# interfacez_main_r2_5.net
KiCad netlist of a schematic drawn in EAGLE
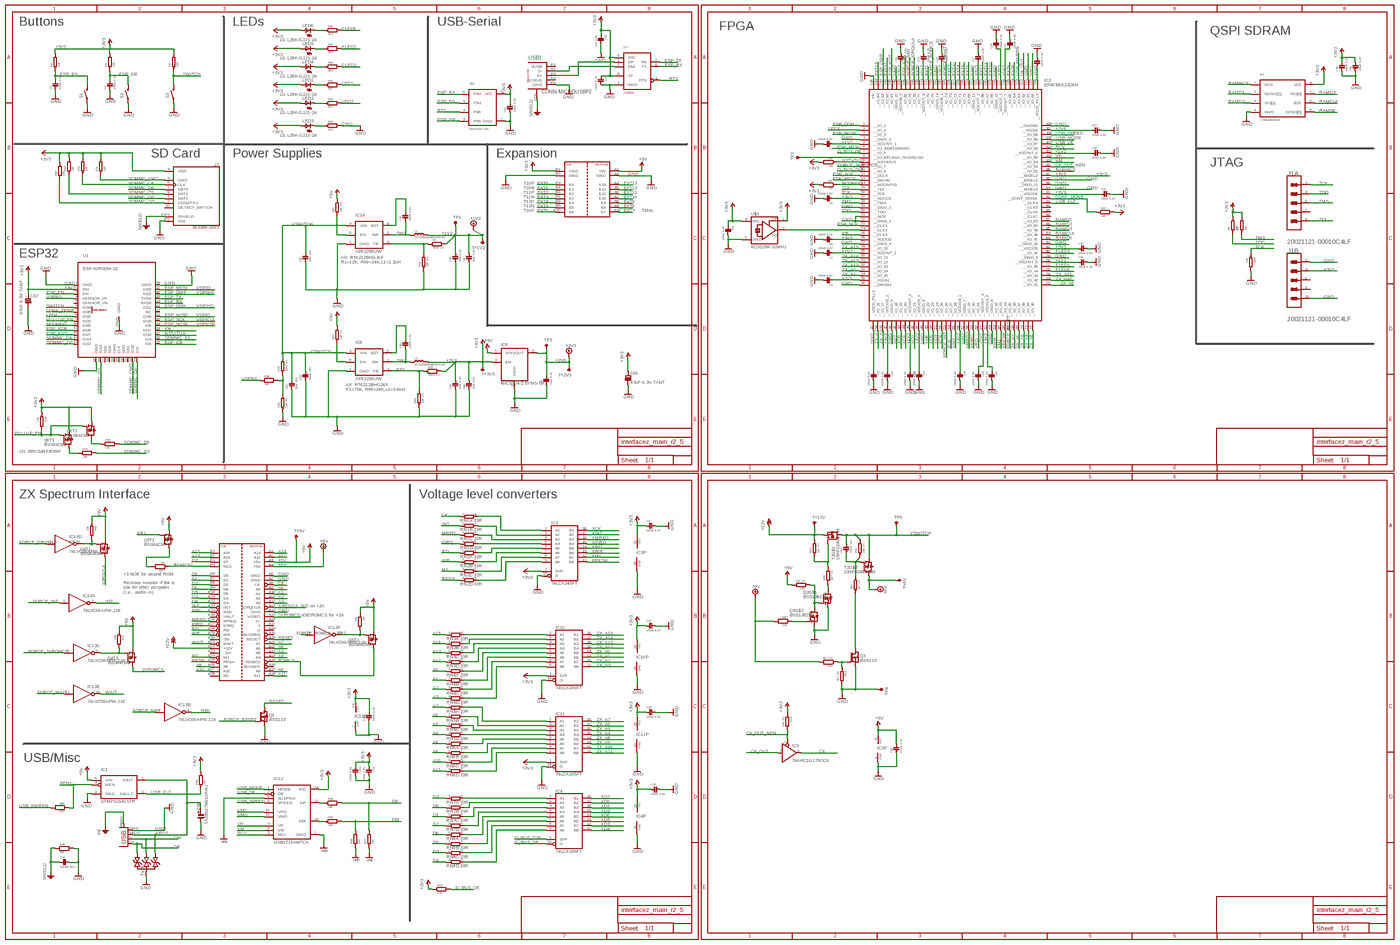
[diagram p0: schematic, sheet 1, overview]
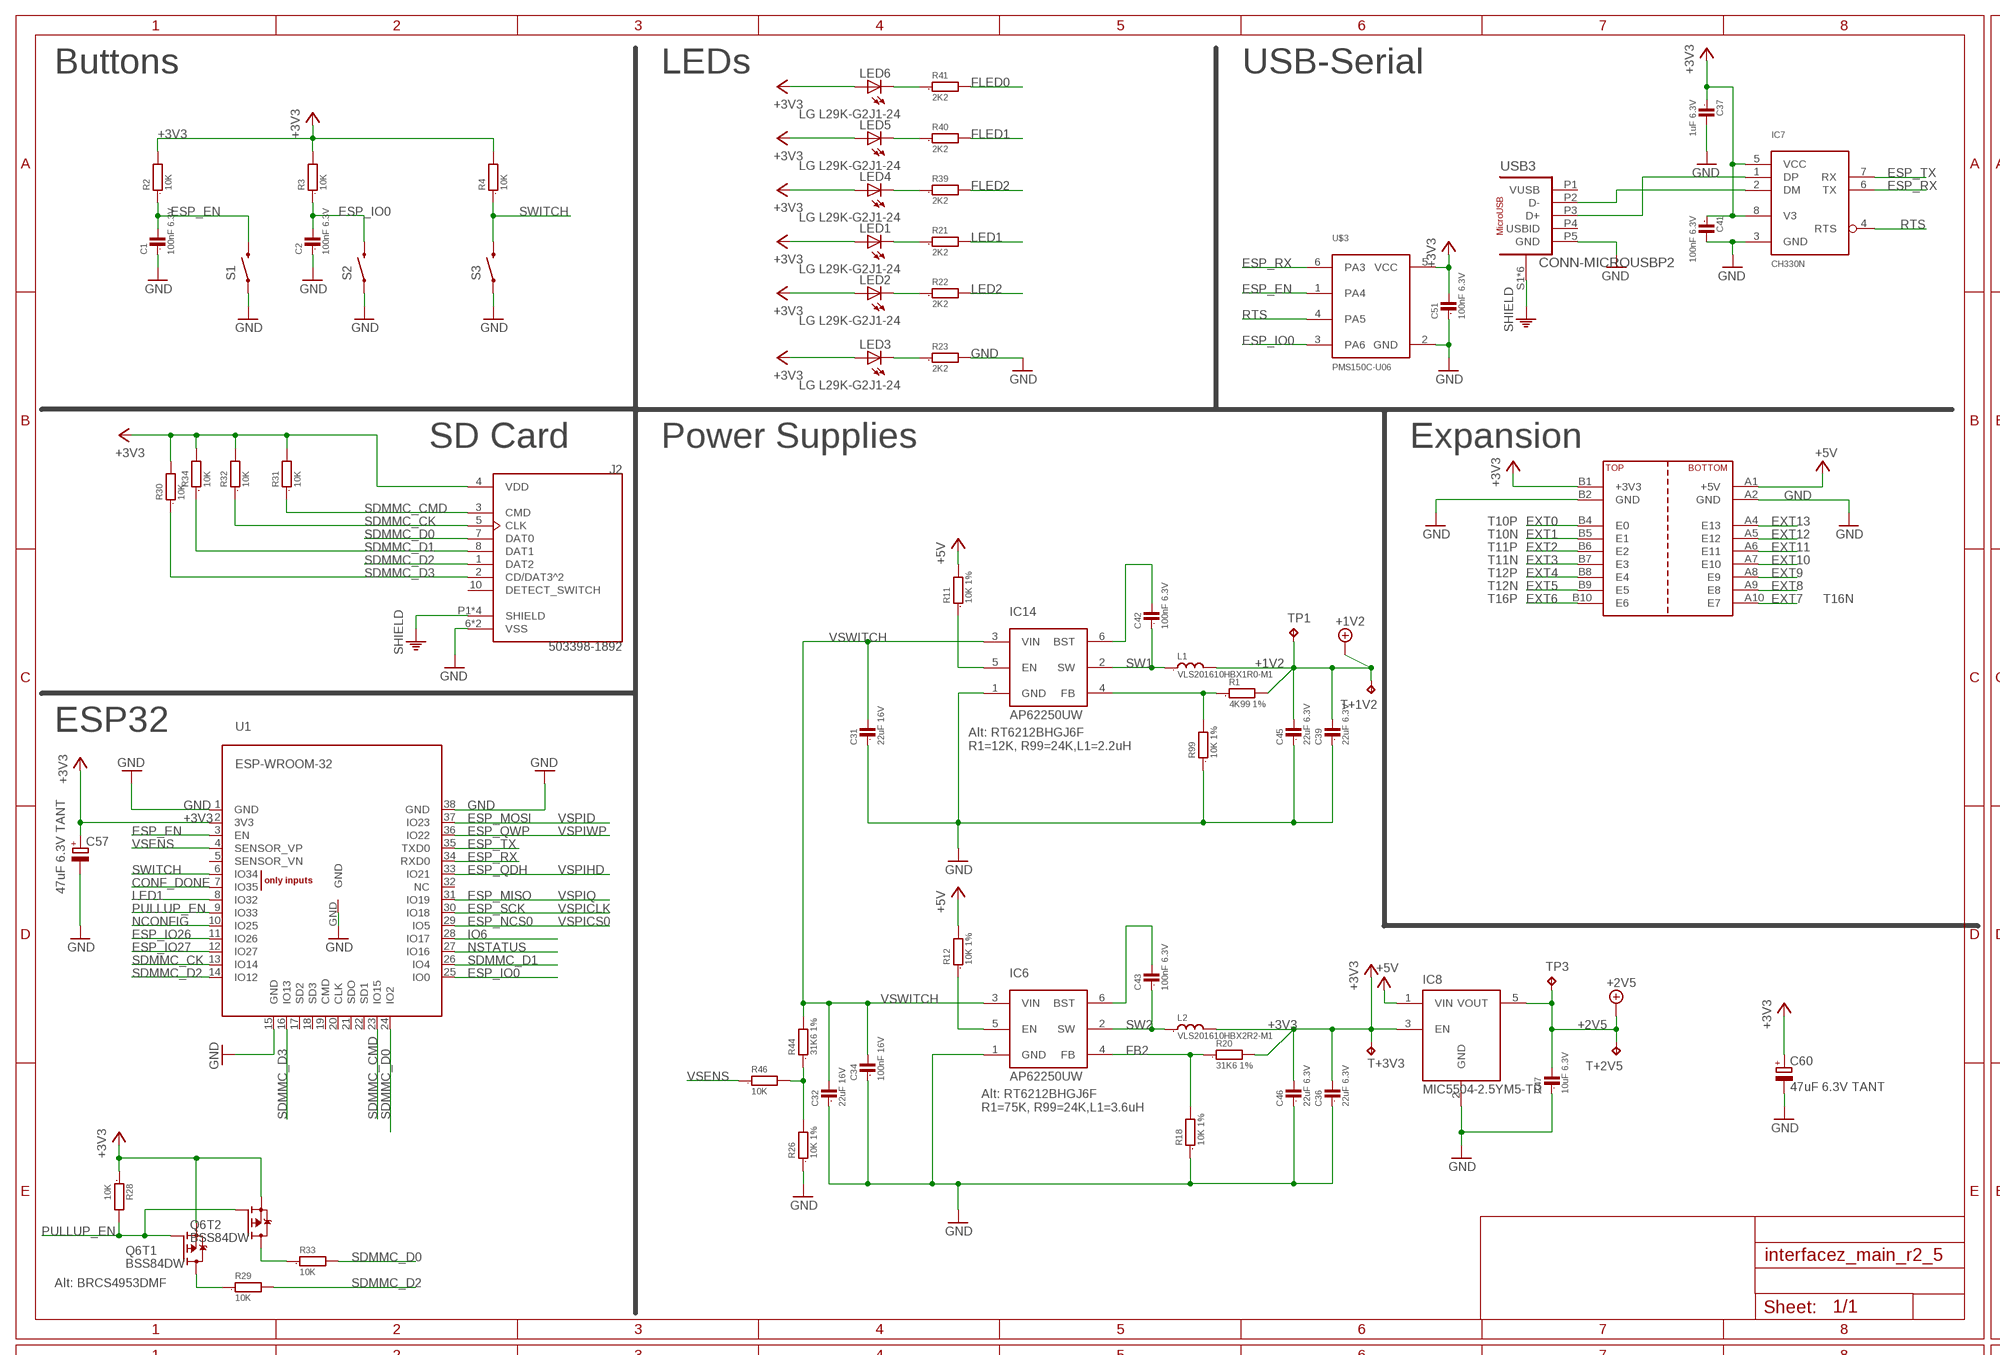
[diagram p1: schematic, sheet 1, part 1 of 4]
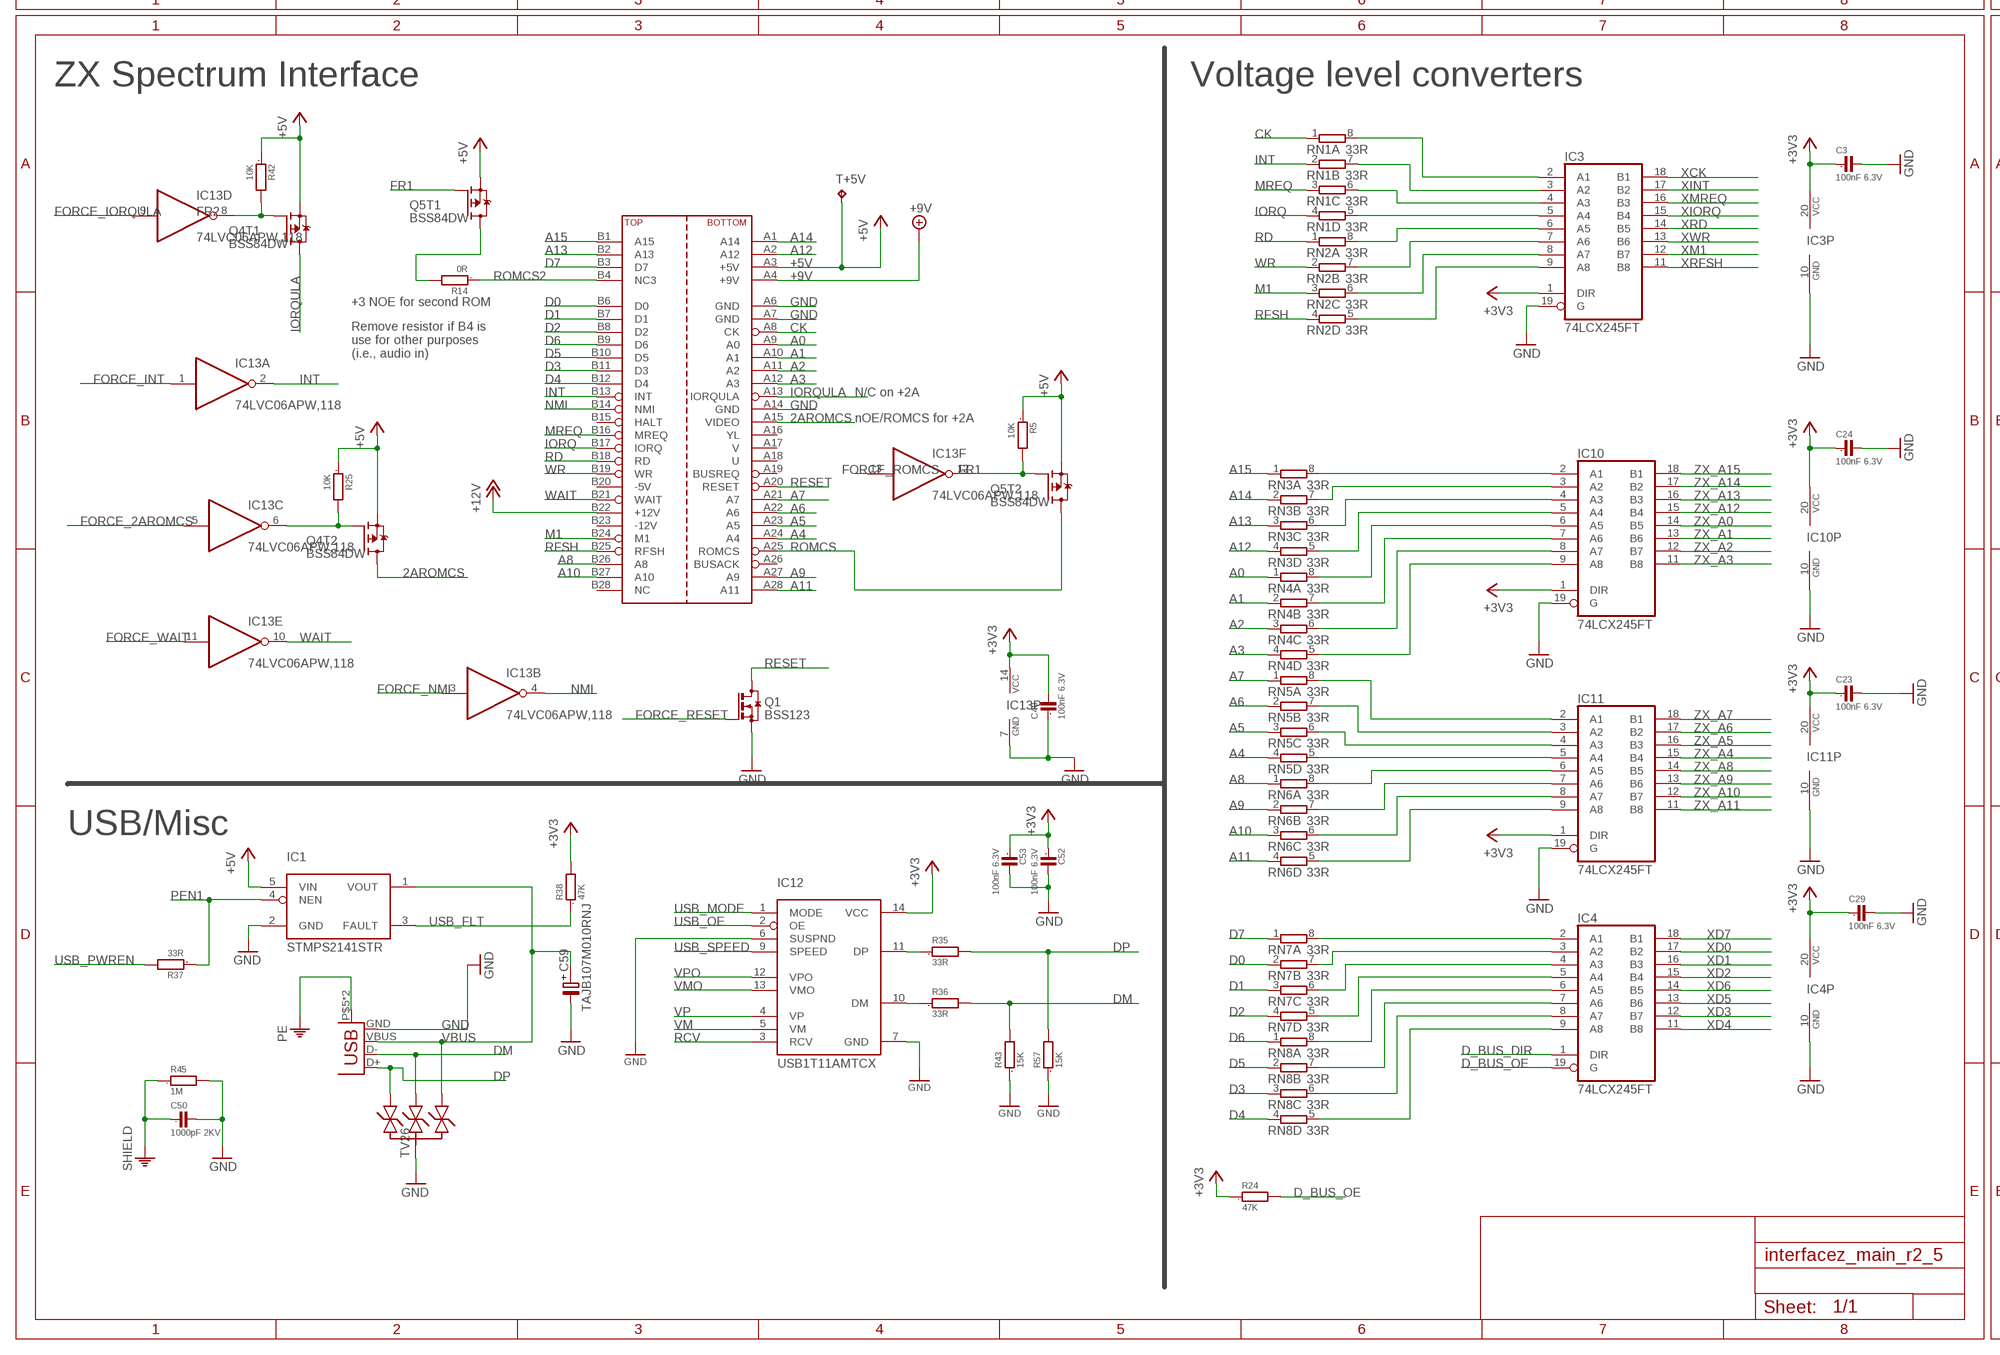
[diagram p2: schematic, sheet 1, part 2 of 4]
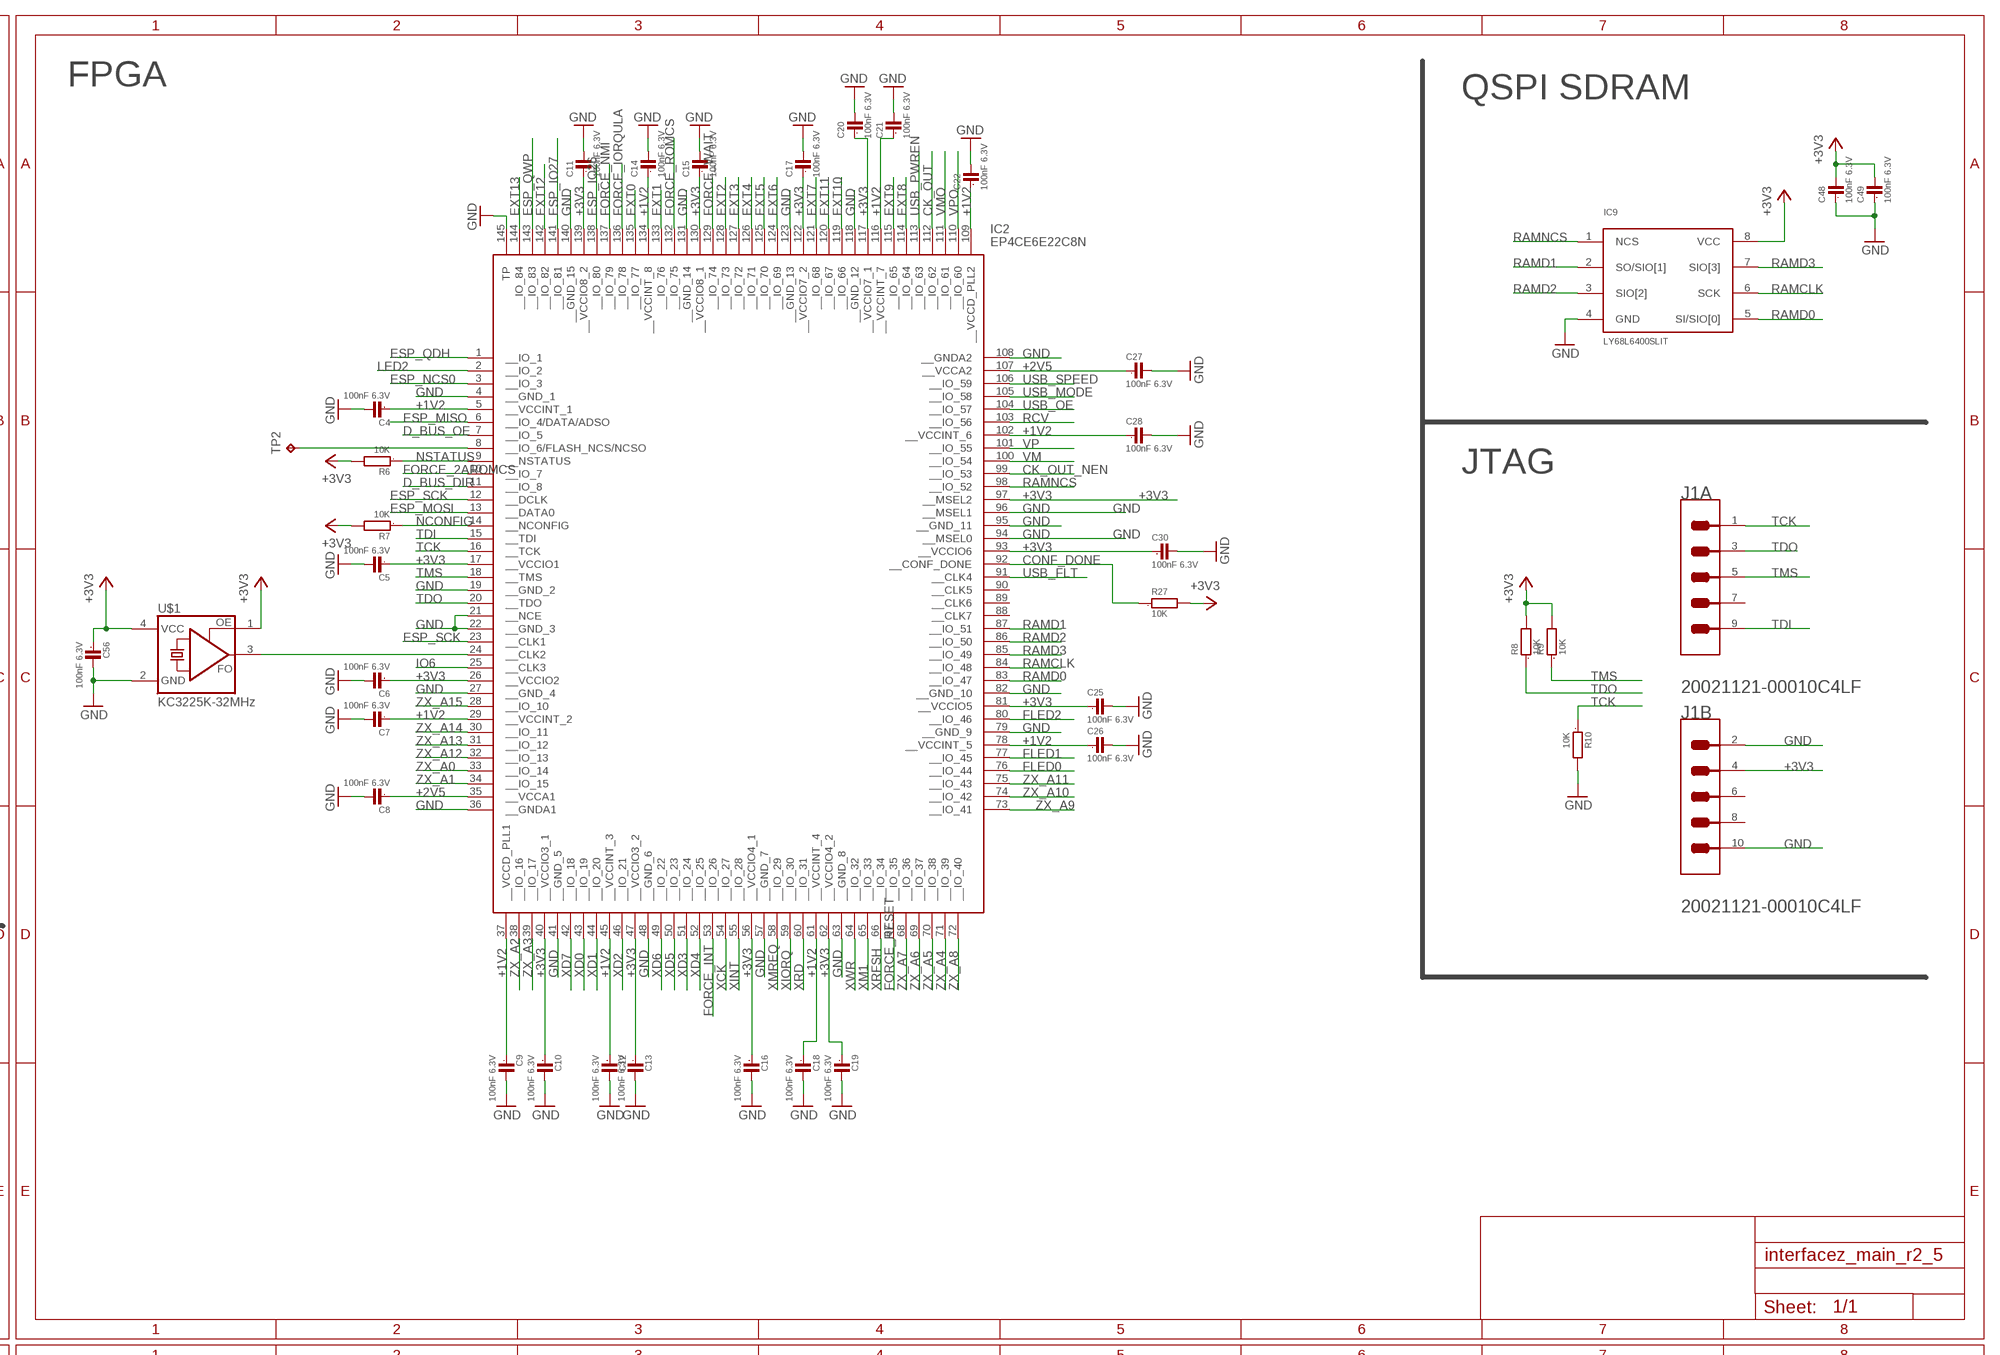
[diagram p3: schematic, sheet 1, part 3 of 4]
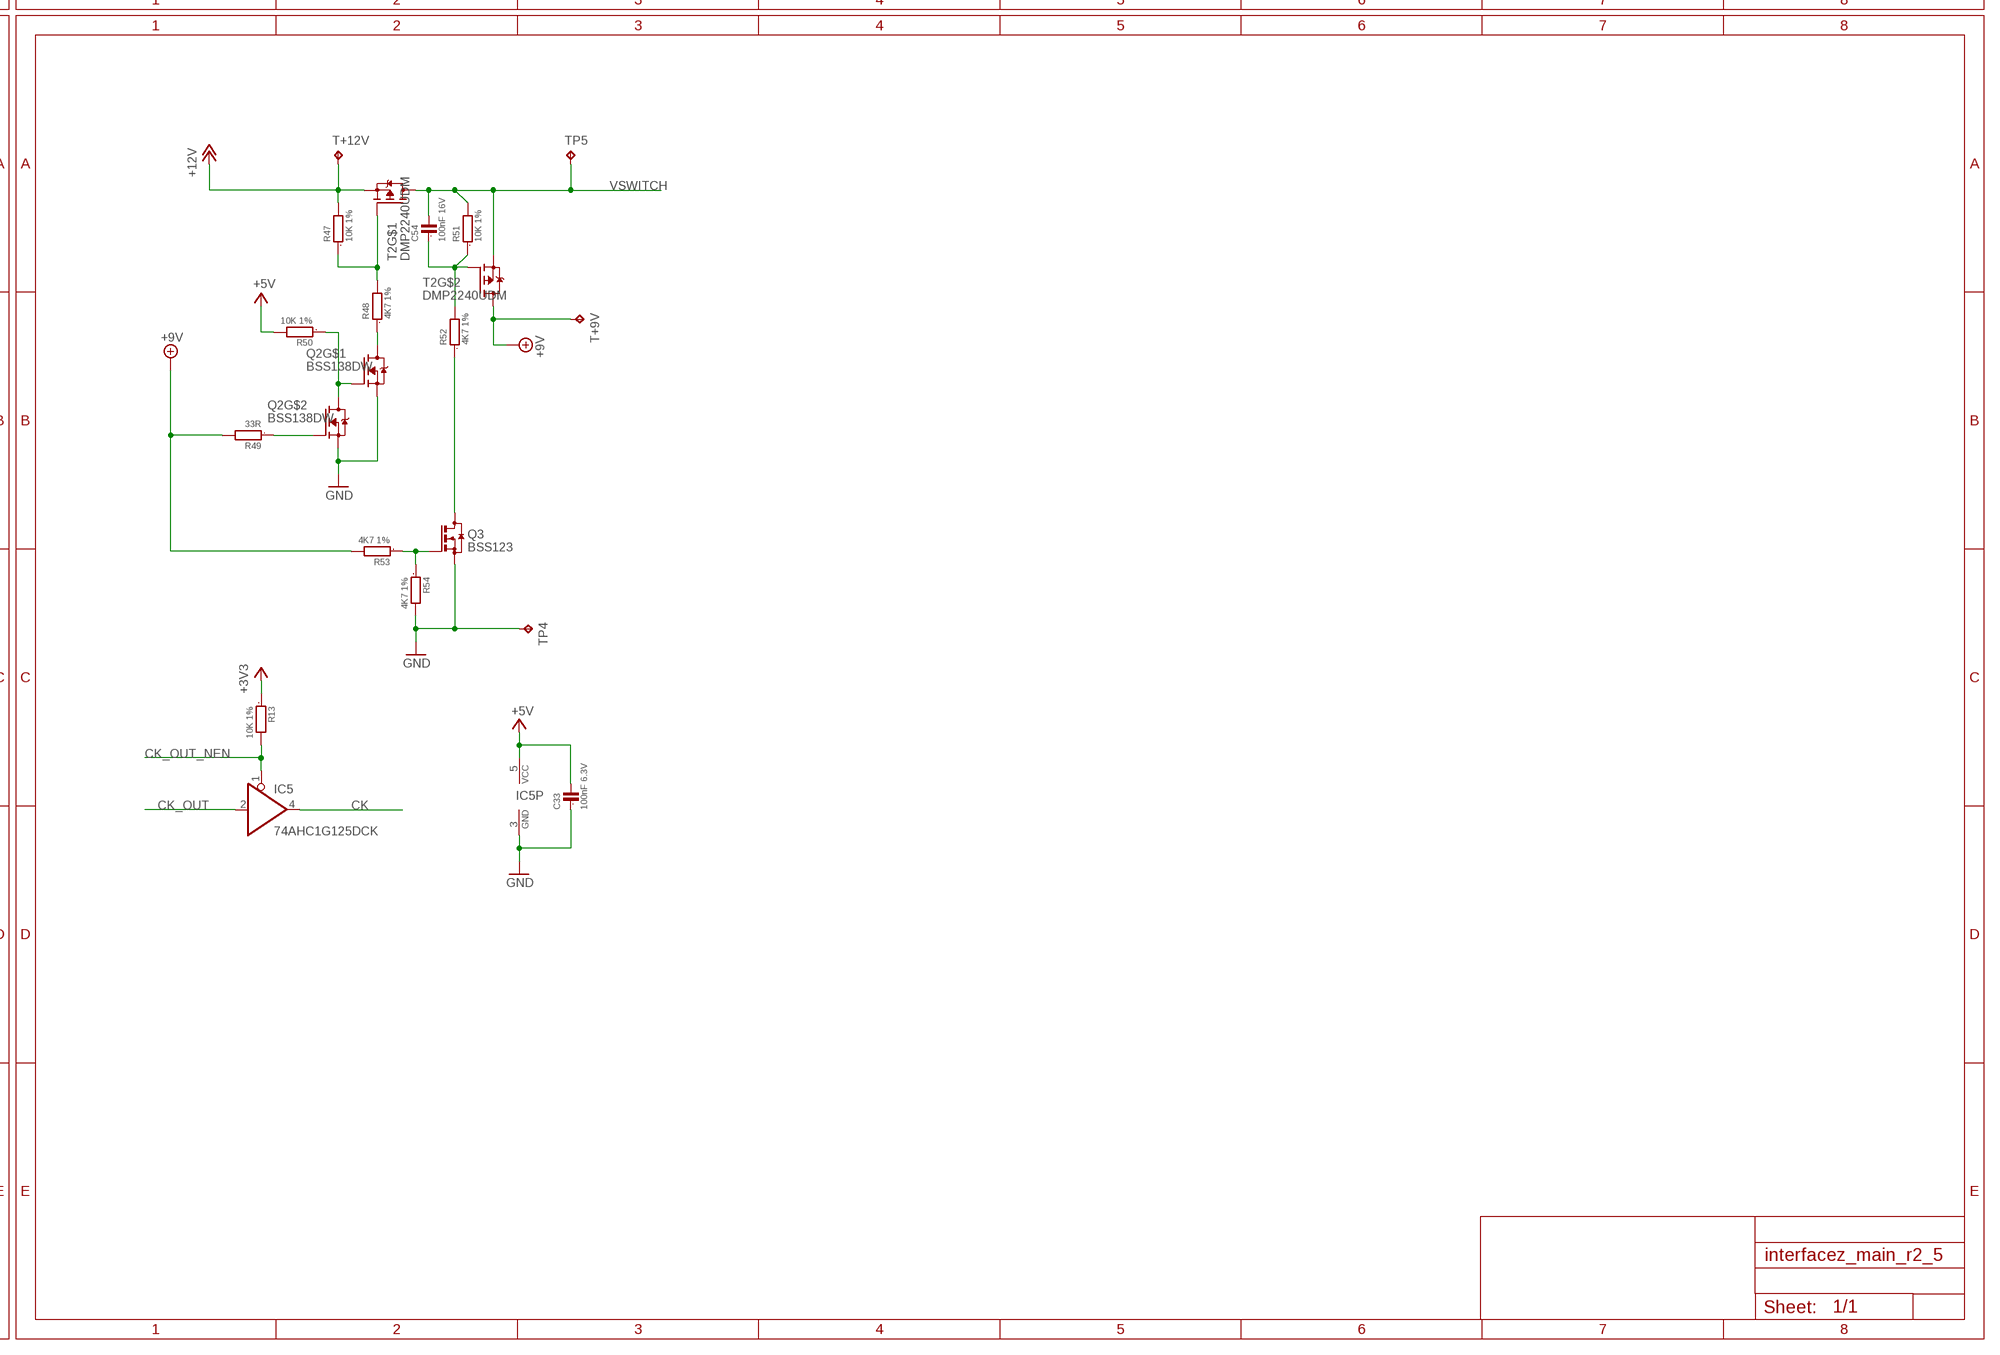
[diagram p4: schematic, sheet 1, part 4 of 4]

(export (version "E")
  (design (tool "Eeschema 10.0.6"))
  (components
    (comp (ref "C1")
      (value "100nF 6.3V")
      (footprint "eagle-import:0603")
      (libsource (lib "eagle-import") (part "C0603"))
    )
    (comp (ref "C2")
      (value "100nF 6.3V")
      (footprint "eagle-import:0603")
      (libsource (lib "eagle-import") (part "C0603"))
    )
    (comp (ref "C3")
      (value "100nF 6.3V")
      (footprint "eagle-import:0603")
      (libsource (lib "eagle-import") (part "C0603"))
    )
    (comp (ref "C4")
      (value "100nF 6.3V")
      (footprint "eagle-import:0603")
      (libsource (lib "eagle-import") (part "C0603"))
    )
    (comp (ref "C5")
      (value "100nF 6.3V")
      (footprint "eagle-import:0603")
      (libsource (lib "eagle-import") (part "C0603"))
    )
    (comp (ref "C6")
      (value "100nF 6.3V")
      (footprint "eagle-import:0603")
      (libsource (lib "eagle-import") (part "C0603"))
    )
    (comp (ref "C7")
      (value "100nF 6.3V")
      (footprint "eagle-import:0603")
      (libsource (lib "eagle-import") (part "C0603"))
    )
    (comp (ref "C8")
      (value "100nF 6.3V")
      (footprint "eagle-import:0603")
      (libsource (lib "eagle-import") (part "C0603"))
    )
    (comp (ref "C9")
      (value "100nF 6.3V")
      (footprint "eagle-import:0603")
      (libsource (lib "eagle-import") (part "C0603"))
    )
    (comp (ref "C10")
      (value "100nF 6.3V")
      (footprint "eagle-import:0603")
      (libsource (lib "eagle-import") (part "C0603"))
    )
    (comp (ref "C11")
      (value "100nF 6.3V")
      (footprint "eagle-import:0603")
      (libsource (lib "eagle-import") (part "C0603"))
    )
    (comp (ref "C12")
      (value "100nF 6.3V")
      (footprint "eagle-import:0603")
      (libsource (lib "eagle-import") (part "C0603"))
    )
    (comp (ref "C13")
      (value "100nF 6.3V")
      (footprint "eagle-import:0603")
      (libsource (lib "eagle-import") (part "C0603"))
    )
    (comp (ref "C14")
      (value "100nF 6.3V")
      (footprint "eagle-import:0603")
      (libsource (lib "eagle-import") (part "C0603"))
    )
    (comp (ref "C15")
      (value "100nF 6.3V")
      (footprint "eagle-import:0603")
      (libsource (lib "eagle-import") (part "C0603"))
    )
    (comp (ref "C16")
      (value "100nF 6.3V")
      (footprint "eagle-import:0603")
      (libsource (lib "eagle-import") (part "C0603"))
    )
    (comp (ref "C17")
      (value "100nF 6.3V")
      (footprint "eagle-import:0603")
      (libsource (lib "eagle-import") (part "C0603"))
    )
    (comp (ref "C18")
      (value "100nF 6.3V")
      (footprint "eagle-import:0603")
      (libsource (lib "eagle-import") (part "C0603"))
    )
    (comp (ref "C19")
      (value "100nF 6.3V")
      (footprint "eagle-import:0603")
      (libsource (lib "eagle-import") (part "C0603"))
    )
    (comp (ref "C20")
      (value "100nF 6.3V")
      (footprint "eagle-import:0603")
      (libsource (lib "eagle-import") (part "C0603"))
    )
    (comp (ref "C21")
      (value "100nF 6.3V")
      (footprint "eagle-import:0603")
      (libsource (lib "eagle-import") (part "C0603"))
    )
    (comp (ref "C22")
      (value "100nF 6.3V")
      (footprint "eagle-import:0603")
      (libsource (lib "eagle-import") (part "C0603"))
    )
    (comp (ref "C23")
      (value "100nF 6.3V")
      (footprint "eagle-import:0603")
      (libsource (lib "eagle-import") (part "C0603"))
    )
    (comp (ref "C24")
      (value "100nF 6.3V")
      (footprint "eagle-import:0603")
      (libsource (lib "eagle-import") (part "C0603"))
    )
    (comp (ref "C25")
      (value "100nF 6.3V")
      (footprint "eagle-import:0603")
      (libsource (lib "eagle-import") (part "C0603"))
    )
    (comp (ref "C26")
      (value "100nF 6.3V")
      (footprint "eagle-import:0603")
      (libsource (lib "eagle-import") (part "C0603"))
    )
    (comp (ref "C27")
      (value "100nF 6.3V")
      (footprint "eagle-import:0603")
      (libsource (lib "eagle-import") (part "C0603"))
    )
    (comp (ref "C28")
      (value "100nF 6.3V")
      (footprint "eagle-import:0603")
      (libsource (lib "eagle-import") (part "C0603"))
    )
    (comp (ref "C29")
      (value "100nF 6.3V")
      (footprint "eagle-import:0603")
      (libsource (lib "eagle-import") (part "C0603"))
    )
    (comp (ref "C30")
      (value "100nF 6.3V")
      (footprint "eagle-import:0603")
      (libsource (lib "eagle-import") (part "C0603"))
    )
    (comp (ref "C31")
      (value "22uF 16V")
      (footprint "eagle-import:1210")
      (libsource (lib "eagle-import") (part "C1210"))
    )
    (comp (ref "C32")
      (value "22uF 16V")
      (footprint "eagle-import:1210")
      (libsource (lib "eagle-import") (part "C1210"))
    )
    (comp (ref "C33")
      (value "100nF 6.3V")
      (footprint "eagle-import:0603")
      (libsource (lib "eagle-import") (part "C0603"))
    )
    (comp (ref "C34")
      (value "100nF 16V")
      (footprint "eagle-import:0603")
      (libsource (lib "eagle-import") (part "C0603"))
    )
    (comp (ref "C36")
      (value "22uF 6.3V")
      (footprint "eagle-import:0805")
      (libsource (lib "eagle-import") (part "C0805"))
    )
    (comp (ref "C37")
      (value "1uF 6.3V")
      (footprint "eagle-import:0603")
      (libsource (lib "eagle-import") (part "C0603"))
    )
    (comp (ref "C39")
      (value "22uF 6.3V")
      (footprint "eagle-import:0805")
      (libsource (lib "eagle-import") (part "C0805"))
    )
    (comp (ref "C40")
      (value "100nF 6.3V")
      (footprint "eagle-import:0603")
      (libsource (lib "eagle-import") (part "C0603"))
    )
    (comp (ref "C41")
      (value "100nF 6.3V")
      (footprint "eagle-import:0603")
      (libsource (lib "eagle-import") (part "C0603"))
    )
    (comp (ref "C42")
      (value "100nF 6.3V")
      (footprint "eagle-import:0603")
      (libsource (lib "eagle-import") (part "C0603"))
    )
    (comp (ref "C43")
      (value "100nF 6.3V")
      (footprint "eagle-import:0603")
      (libsource (lib "eagle-import") (part "C0603"))
    )
    (comp (ref "C45")
      (value "22uF 6.3V")
      (footprint "eagle-import:0805")
      (libsource (lib "eagle-import") (part "C0805"))
    )
    (comp (ref "C46")
      (value "22uF 6.3V")
      (footprint "eagle-import:0805")
      (libsource (lib "eagle-import") (part "C0805"))
    )
    (comp (ref "C47")
      (value "10uF 6.3V")
      (footprint "eagle-import:0805")
      (libsource (lib "eagle-import") (part "C0805"))
    )
    (comp (ref "C48")
      (value "100nF 6.3V")
      (footprint "eagle-import:0603")
      (libsource (lib "eagle-import") (part "C0603"))
    )
    (comp (ref "C49")
      (value "100nF 6.3V")
      (footprint "eagle-import:0603")
      (libsource (lib "eagle-import") (part "C0603"))
    )
    (comp (ref "C50")
      (value "1000pF 2KV")
      (footprint "eagle-import:1210")
      (libsource (lib "eagle-import") (part "C1210"))
    )
    (comp (ref "C51")
      (value "100nF 6.3V")
      (footprint "eagle-import:0603")
      (libsource (lib "eagle-import") (part "C0603"))
    )
    (comp (ref "C52")
      (value "100nF 6.3V")
      (footprint "eagle-import:0603")
      (libsource (lib "eagle-import") (part "C0603"))
    )
    (comp (ref "C53")
      (value "100nF 6.3V")
      (footprint "eagle-import:0603")
      (libsource (lib "eagle-import") (part "C0603"))
    )
    (comp (ref "C54")
      (value "100nF 16V")
      (footprint "eagle-import:0603")
      (libsource (lib "eagle-import") (part "C0603"))
    )
    (comp (ref "C56")
      (value "100nF 6.3V")
      (footprint "eagle-import:0603")
      (libsource (lib "eagle-import") (part "C0603"))
    )
    (comp (ref "C57")
      (value "47uF 6.3V TANT")
      (footprint "eagle-import:TANT_CASE_A")
      (libsource (lib "eagle-import") (part "TANT_CASE_A"))
    )
    (comp (ref "C59")
      (value "TAJB107M010RNJ")
      (footprint "eagle-import:TE-B-3528")
      (libsource (lib "eagle-import") (part "C-PR-SMD-TE-B"))
    )
    (comp (ref "C60")
      (value "47uF 6.3V TANT")
      (footprint "eagle-import:TANT_CASE_A")
      (libsource (lib "eagle-import") (part "TANT_CASE_A"))
    )
    (comp (ref "CONN1")
      (value "ZX_EDGE_DAUGHTERBOARD")
      (footprint "eagle-import:ZX-EDGE-DAUGHTERBOARD")
      (libsource (lib "eagle-import") (part "ZX_EDGE_DAUGHTERBOARD"))
    )
    (comp (ref "IC1")
      (value "STMPS2141STR")
      (footprint "eagle-import:SOT23-5L")
      (libsource (lib "eagle-import") (part "STMPS2141STR"))
    )
    (comp (ref "IC2")
      (value "EP4CE6E22C8N")
      (footprint "eagle-import:QFP50P2200X2200X165-145N")
      (fields (field (name "MOUSER_PART_NUMBER") "989-EP4CE6E22C8N"))
      (libsource (lib "eagle-import") (part "EP4CE6E22C8N"))
    )
    (comp (ref "IC3")
      (value "74LCX245FT")
      (footprint "eagle-import:TSSOP20")
      (libsource (lib "eagle-import") (part "74245"))
    )
    (comp (ref "IC4")
      (value "74LCX245FT")
      (footprint "eagle-import:TSSOP20")
      (libsource (lib "eagle-import") (part "74245"))
    )
    (comp (ref "IC5")
      (value "74AHC1G125DCK")
      (footprint "eagle-import:SC70-5")
      (libsource (lib "eagle-import") (part "741G125DCKAHC"))
    )
    (comp (ref "IC6")
      (value "AP62250UW")
      (footprint "eagle-import:SOT23-6")
      (libsource (lib "eagle-import") (part "AP62250UW"))
    )
    (comp (ref "IC7")
      (value "CH330N")
      (footprint "eagle-import:SOIC8")
      (libsource (lib "eagle-import") (part "CH330N"))
    )
    (comp (ref "IC8")
      (value "MIC5504-2.5YM5-TR")
      (footprint "eagle-import:SOT23-5L")
      (libsource (lib "eagle-import") (part "MIC550X"))
    )
    (comp (ref "IC9")
      (value "LY68L6400SLIT")
      (footprint "eagle-import:SOIC8")
      (libsource (lib "eagle-import") (part "LY68L6400SLIT"))
    )
    (comp (ref "IC10")
      (value "74LCX245FT")
      (footprint "eagle-import:TSSOP20")
      (libsource (lib "eagle-import") (part "74245"))
    )
    (comp (ref "IC11")
      (value "74LCX245FT")
      (footprint "eagle-import:TSSOP20")
      (libsource (lib "eagle-import") (part "74245"))
    )
    (comp (ref "IC12")
      (value "USB1T11AMTCX")
      (footprint "eagle-import:TSSOP14")
      (libsource (lib "eagle-import") (part "USB1TMTCX11A"))
    )
    (comp (ref "IC13")
      (value "74LVC06APW,118")
      (footprint "eagle-import:TSSOP14")
      (libsource (lib "eagle-import") (part "7406APW,118LVC"))
    )
    (comp (ref "IC14")
      (value "AP62250UW")
      (footprint "eagle-import:SOT23-6")
      (libsource (lib "eagle-import") (part "AP62250UW"))
    )
    (comp (ref "J1")
      (value "AMPHENOL_ICC_-_FCI_20021121-00010C4LFAMPHENOL_ICC_-_FCI_20021121-00010C4LF_0_0")
      (footprint "eagle-import:AMPHENOL_ICC_-_FCI_20021121-00010C4LF_0")
      (fields
        (field (name "DIGIKEY_PART_NUMBER") "609-3695-1-ND")
        (field (name "MF") "Amphenol ICC / FCI")
        (field (name "MOUSER_PART_NUMBER") "649-202112100010C4LF")
      )
      (libsource (lib "eagle-import") (part "AMPHENOL_ICC_-_FCI_20021121-00010C4LFAMPHENOL_ICC_-_FCI_20021121-00010C4LF_0_0"))
    )
    (comp (ref "J2")
      (value "503398-1892")
      (footprint "eagle-import:MOLEX_503398-1892")
      (fields (field (name "MF") "Molex"))
      (libsource (lib "eagle-import") (part "503398-1892"))
    )
    (comp (ref "L1")
      (value "VLS201610HBX1R0-M1")
      (footprint "eagle-import:IND_0806")
      (libsource (lib "eagle-import") (part "VLS201610HBXR68-M1"))
    )
    (comp (ref "L2")
      (value "VLS201610HBX2R2-M1")
      (footprint "eagle-import:IND_0806")
      (libsource (lib "eagle-import") (part "VLS201610HBX1R5-M1"))
    )
    (comp (ref "LED1")
      (value "LG L29K-G2J1-24")
      (footprint "eagle-import:LED-603")
      (libsource (lib "eagle-import") (part "LED-0603"))
    )
    (comp (ref "LED2")
      (value "LG L29K-G2J1-24")
      (footprint "eagle-import:LED-603")
      (libsource (lib "eagle-import") (part "LED-0603"))
    )
    (comp (ref "LED3")
      (value "LG L29K-G2J1-24")
      (footprint "eagle-import:LED-603")
      (libsource (lib "eagle-import") (part "LED-0603"))
    )
    (comp (ref "LED4")
      (value "LG L29K-G2J1-24")
      (footprint "eagle-import:LED-603")
      (libsource (lib "eagle-import") (part "LED-0603"))
    )
    (comp (ref "LED5")
      (value "LG L29K-G2J1-24")
      (footprint "eagle-import:LED-603")
      (libsource (lib "eagle-import") (part "LED-0603"))
    )
    (comp (ref "LED6")
      (value "LG L29K-G2J1-24")
      (footprint "eagle-import:LED-603")
      (libsource (lib "eagle-import") (part "LED-0603"))
    )
    (comp (ref "Q1")
      (value "BSS123")
      (footprint "eagle-import:SOT23")
      (libsource (lib "eagle-import") (part "BSS123"))
    )
    (comp (ref "Q2")
      (value "BSS138DW")
      (footprint "eagle-import:SOT363_INFINEON")
      (libsource (lib "eagle-import") (part "BSS138DW"))
    )
    (comp (ref "Q3")
      (value "BSS123")
      (footprint "eagle-import:SOT23")
      (libsource (lib "eagle-import") (part "BSS123"))
    )
    (comp (ref "Q4")
      (value "BSS84DW")
      (footprint "eagle-import:SOT363_INFINEON")
      (libsource (lib "eagle-import") (part "BSS84DW"))
    )
    (comp (ref "Q5")
      (value "BSS84DW")
      (footprint "eagle-import:SOT363_INFINEON")
      (libsource (lib "eagle-import") (part "BSS84DW"))
    )
    (comp (ref "Q6")
      (value "BSS84DW")
      (footprint "eagle-import:SOT363_INFINEON")
      (libsource (lib "eagle-import") (part "BSS84DW"))
    )
    (comp (ref "R1")
      (value "4K99 1%")
      (footprint "eagle-import:0603")
      (libsource (lib "eagle-import") (part "R0603"))
    )
    (comp (ref "R2")
      (value "10K")
      (footprint "eagle-import:0603")
      (libsource (lib "eagle-import") (part "R0603"))
    )
    (comp (ref "R3")
      (value "10K")
      (footprint "eagle-import:0603")
      (libsource (lib "eagle-import") (part "R0603"))
    )
    (comp (ref "R4")
      (value "10K")
      (footprint "eagle-import:0603")
      (libsource (lib "eagle-import") (part "R0603"))
    )
    (comp (ref "R5")
      (value "10K")
      (footprint "eagle-import:0603")
      (libsource (lib "eagle-import") (part "R0603"))
    )
    (comp (ref "R6")
      (value "10K")
      (footprint "eagle-import:0603")
      (libsource (lib "eagle-import") (part "R0603"))
    )
    (comp (ref "R7")
      (value "10K")
      (footprint "eagle-import:0603")
      (libsource (lib "eagle-import") (part "R0603"))
    )
    (comp (ref "R8")
      (value "10K")
      (footprint "eagle-import:0603")
      (libsource (lib "eagle-import") (part "R0603"))
    )
    (comp (ref "R9")
      (value "10K")
      (footprint "eagle-import:0603")
      (libsource (lib "eagle-import") (part "R0603"))
    )
    (comp (ref "R10")
      (value "10K")
      (footprint "eagle-import:0603")
      (libsource (lib "eagle-import") (part "R0603"))
    )
    (comp (ref "R11")
      (value "10K 1%")
      (footprint "eagle-import:0603")
      (libsource (lib "eagle-import") (part "R0603"))
    )
    (comp (ref "R12")
      (value "10K 1%")
      (footprint "eagle-import:0603")
      (libsource (lib "eagle-import") (part "R0603"))
    )
    (comp (ref "R13")
      (value "10K 1%")
      (footprint "eagle-import:0603")
      (libsource (lib "eagle-import") (part "R0603"))
    )
    (comp (ref "R14")
      (value "0R")
      (footprint "eagle-import:0603")
      (libsource (lib "eagle-import") (part "R0603"))
    )
    (comp (ref "R18")
      (value "10K 1%")
      (footprint "eagle-import:0603")
      (libsource (lib "eagle-import") (part "R0603"))
    )
    (comp (ref "R20")
      (value "31K6 1%")
      (footprint "eagle-import:0603")
      (libsource (lib "eagle-import") (part "R0603"))
    )
    (comp (ref "R21")
      (value "2K2")
      (footprint "eagle-import:0603")
      (libsource (lib "eagle-import") (part "R0603"))
    )
    (comp (ref "R22")
      (value "2K2")
      (footprint "eagle-import:0603")
      (libsource (lib "eagle-import") (part "R0603"))
    )
    (comp (ref "R23")
      (value "2K2")
      (footprint "eagle-import:0603")
      (libsource (lib "eagle-import") (part "R0603"))
    )
    (comp (ref "R24")
      (value "47K")
      (footprint "eagle-import:0603")
      (libsource (lib "eagle-import") (part "R0603"))
    )
    (comp (ref "R25")
      (value "10K")
      (footprint "eagle-import:0603")
      (libsource (lib "eagle-import") (part "R0603"))
    )
    (comp (ref "R26")
      (value "10K 1%")
      (footprint "eagle-import:0603")
      (libsource (lib "eagle-import") (part "R0603"))
    )
    (comp (ref "R27")
      (value "10K")
      (footprint "eagle-import:0603")
      (libsource (lib "eagle-import") (part "R0603"))
    )
    (comp (ref "R28")
      (value "10K")
      (footprint "eagle-import:0603")
      (libsource (lib "eagle-import") (part "R0603"))
    )
    (comp (ref "R29")
      (value "10K")
      (footprint "eagle-import:0603")
      (libsource (lib "eagle-import") (part "R0603"))
    )
    (comp (ref "R30")
      (value "10K")
      (footprint "eagle-import:0603")
      (libsource (lib "eagle-import") (part "R0603"))
    )
    (comp (ref "R31")
      (value "10K")
      (footprint "eagle-import:0603")
      (libsource (lib "eagle-import") (part "R0603"))
    )
    (comp (ref "R32")
      (value "10K")
      (footprint "eagle-import:0603")
      (libsource (lib "eagle-import") (part "R0603"))
    )
    (comp (ref "R33")
      (value "10K")
      (footprint "eagle-import:0603")
      (libsource (lib "eagle-import") (part "R0603"))
    )
    (comp (ref "R34")
      (value "10K")
      (footprint "eagle-import:0603")
      (libsource (lib "eagle-import") (part "R0603"))
    )
    (comp (ref "R35")
      (value "33R")
      (footprint "eagle-import:0603")
      (libsource (lib "eagle-import") (part "R0603"))
    )
    (comp (ref "R36")
      (value "33R")
      (footprint "eagle-import:0603")
      (libsource (lib "eagle-import") (part "R0603"))
    )
    (comp (ref "R37")
      (value "33R")
      (footprint "eagle-import:0603")
      (libsource (lib "eagle-import") (part "R0603"))
    )
    (comp (ref "R38")
      (value "47K")
      (footprint "eagle-import:0603")
      (libsource (lib "eagle-import") (part "R0603"))
    )
    (comp (ref "R39")
      (value "2K2")
      (footprint "eagle-import:0603")
      (libsource (lib "eagle-import") (part "R0603"))
    )
    (comp (ref "R40")
      (value "2K2")
      (footprint "eagle-import:0603")
      (libsource (lib "eagle-import") (part "R0603"))
    )
    (comp (ref "R41")
      (value "2K2")
      (footprint "eagle-import:0603")
      (libsource (lib "eagle-import") (part "R0603"))
    )
    (comp (ref "R42")
      (value "10K")
      (footprint "eagle-import:0603")
      (libsource (lib "eagle-import") (part "R0603"))
    )
    (comp (ref "R43")
      (value "15K")
      (footprint "eagle-import:0603")
      (libsource (lib "eagle-import") (part "R0603"))
    )
    (comp (ref "R44")
      (value "31K6 1%")
      (footprint "eagle-import:0603")
      (libsource (lib "eagle-import") (part "R0603"))
    )
    (comp (ref "R45")
      (value "1M")
      (footprint "eagle-import:0805")
      (libsource (lib "eagle-import") (part "R0805"))
    )
    (comp (ref "R46")
      (value "10K")
      (footprint "eagle-import:0603")
      (libsource (lib "eagle-import") (part "R0603"))
    )
    (comp (ref "R47")
      (value "10K 1%")
      (footprint "eagle-import:0603")
      (libsource (lib "eagle-import") (part "R0603"))
    )
    (comp (ref "R48")
      (value "4K7 1%")
      (footprint "eagle-import:0603")
      (libsource (lib "eagle-import") (part "R0603"))
    )
    (comp (ref "R49")
      (value "33R")
      (footprint "eagle-import:0603")
      (libsource (lib "eagle-import") (part "R0603"))
    )
    (comp (ref "R50")
      (value "10K 1%")
      (footprint "eagle-import:0603")
      (libsource (lib "eagle-import") (part "R0603"))
    )
    (comp (ref "R51")
      (value "10K 1%")
      (footprint "eagle-import:0603")
      (libsource (lib "eagle-import") (part "R0603"))
    )
    (comp (ref "R52")
      (value "4K7 1%")
      (footprint "eagle-import:0603")
      (libsource (lib "eagle-import") (part "R0603"))
    )
    (comp (ref "R53")
      (value "4K7 1%")
      (footprint "eagle-import:0603")
      (libsource (lib "eagle-import") (part "R0603"))
    )
    (comp (ref "R54")
      (value "4K7 1%")
      (footprint "eagle-import:0603")
      (libsource (lib "eagle-import") (part "R0603"))
    )
    (comp (ref "R57")
      (value "15K")
      (footprint "eagle-import:0603")
      (libsource (lib "eagle-import") (part "R0603"))
    )
    (comp (ref "R99")
      (value "10K 1%")
      (footprint "eagle-import:0603")
      (libsource (lib "eagle-import") (part "R0603"))
    )
    (comp (ref "RN1")
      (value "33R")
      (footprint "eagle-import:EXB28V")
      (libsource (lib "eagle-import") (part "4R-NEXB28V"))
    )
    (comp (ref "RN2")
      (value "33R")
      (footprint "eagle-import:EXB28V")
      (libsource (lib "eagle-import") (part "4R-NEXB28V"))
    )
    (comp (ref "RN3")
      (value "33R")
      (footprint "eagle-import:EXB28V")
      (libsource (lib "eagle-import") (part "4R-NEXB28V"))
    )
    (comp (ref "RN4")
      (value "33R")
      (footprint "eagle-import:EXB28V")
      (libsource (lib "eagle-import") (part "4R-NEXB28V"))
    )
    (comp (ref "RN5")
      (value "33R")
      (footprint "eagle-import:EXB28V")
      (libsource (lib "eagle-import") (part "4R-NEXB28V"))
    )
    (comp (ref "RN6")
      (value "33R")
      (footprint "eagle-import:EXB28V")
      (libsource (lib "eagle-import") (part "4R-NEXB28V"))
    )
    (comp (ref "RN7")
      (value "33R")
      (footprint "eagle-import:EXB28V")
      (libsource (lib "eagle-import") (part "4R-NEXB28V"))
    )
    (comp (ref "RN8")
      (value "33R")
      (footprint "eagle-import:EXB28V")
      (libsource (lib "eagle-import") (part "4R-NEXB28V"))
    )
    (comp (ref "S1")
      (value "SWITCHES_SMD-4")
      (footprint "eagle-import:TACTILE_SWITCH_TALL")
      (libsource (lib "eagle-import") (part "SWITCHES_SMD-4"))
    )
    (comp (ref "S2")
      (value "SWITCHES_SMD-4")
      (footprint "eagle-import:TACTILE_SWITCH_TALL")
      (libsource (lib "eagle-import") (part "SWITCHES_SMD-4"))
    )
    (comp (ref "S3")
      (value "SWITCHES_SMD-4")
      (footprint "eagle-import:TACTILE_SWITCH_TALL")
      (libsource (lib "eagle-import") (part "SWITCHES_SMD-4"))
    )
    (comp (ref "T+1V2")
      (value "TPTP12SQ")
      (footprint "eagle-import:TP12SQ")
      (libsource (lib "eagle-import") (part "TPTP12SQ"))
    )
    (comp (ref "T+2V5")
      (value "TPTP12SQ")
      (footprint "eagle-import:TP12SQ")
      (libsource (lib "eagle-import") (part "TPTP12SQ"))
    )
    (comp (ref "T+3V3")
      (value "TPTP12SQ")
      (footprint "eagle-import:TP12SQ")
      (libsource (lib "eagle-import") (part "TPTP12SQ"))
    )
    (comp (ref "T+5V")
      (value "TPTP12SQ")
      (footprint "eagle-import:TP12SQ")
      (libsource (lib "eagle-import") (part "TPTP12SQ"))
    )
    (comp (ref "T+9V")
      (value "TPTP12SQ")
      (footprint "eagle-import:TP12SQ")
      (libsource (lib "eagle-import") (part "TPTP12SQ"))
    )
    (comp (ref "T+12V")
      (value "TPTP12SQ")
      (footprint "eagle-import:TP12SQ")
      (libsource (lib "eagle-import") (part "TPTP12SQ"))
    )
    (comp (ref "T2")
      (value "DMP2240UDM")
      (footprint "eagle-import:SOT23-6")
      (libsource (lib "eagle-import") (part "MOSFET-P-DUAL-SOT23-6"))
    )
    (comp (ref "TP1")
      (value "TPTP12R")
      (footprint "eagle-import:TP12R")
      (libsource (lib "eagle-import") (part "TPTP12R"))
    )
    (comp (ref "TP2")
      (value "TPTP12SQ")
      (footprint "eagle-import:TP12SQ")
      (libsource (lib "eagle-import") (part "TPTP12SQ"))
    )
    (comp (ref "TP3")
      (value "TPTP12R")
      (footprint "eagle-import:TP12R")
      (libsource (lib "eagle-import") (part "TPTP12R"))
    )
    (comp (ref "TP4")
      (value "TPPAD1-13")
      (footprint "eagle-import:P1-13")
      (libsource (lib "eagle-import") (part "TPPAD1-13"))
    )
    (comp (ref "TP5")
      (value "TPTP12SQ")
      (footprint "eagle-import:TP12SQ")
      (libsource (lib "eagle-import") (part "TPTP12SQ"))
    )
    (comp (ref "TV26")
      (value "SP0503BAHT")
      (footprint "eagle-import:SP0503")
      (libsource (lib "eagle-import") (part "SP0503BAHT"))
    )
    (comp (ref "U$1")
      (value "KC3225K-32MHz")
      (footprint "eagle-import:KC3225K")
      (libsource (lib "eagle-import") (part "KC3225K"))
    )
    (comp (ref "U$3")
      (value "PMS150C-U06")
      (footprint "eagle-import:SOT23-6")
      (libsource (lib "eagle-import") (part "PMS150C-U06"))
    )
    (comp (ref "U$5")
      (value "INTERFACEZ_EDGEDAUGHTER")
      (footprint "eagle-import:INTERFACEZ_EXPANSION_DAUGHTERCARD")
      (libsource (lib "eagle-import") (part "INTERFACEZ_EDGEDAUGHTER"))
    )
    (comp (ref "U1")
      (value "ESP-WROOM-32")
      (footprint "eagle-import:ESP-WROOM-32")
      (libsource (lib "eagle-import") (part "ESP-WROOM-32"))
    )
    (comp (ref "USB2")
      (value "USB-A-H")
      (footprint "eagle-import:USB-A-H")
      (libsource (lib "eagle-import") (part "USB-A-H"))
    )
    (comp (ref "USB3")
      (value "CONN-MICROUSBP2")
      (footprint "eagle-import:MICROUSB_SMD_TH_7.5MM_4.85MM")
      (libsource (lib "eagle-import") (part "CONN-MICROUSBP2"))
    )
  )
  (nets
    (net (code "1") (name "+1V2") (class "Default")
      (node (ref "C12") (pin "1") (pinfunction "1_1") (pintype "passive"))
      (node (ref "C14") (pin "1") (pinfunction "1_1") (pintype "passive"))
      (node (ref "C18") (pin "1") (pinfunction "1_1") (pintype "passive"))
      (node (ref "C21") (pin "1") (pinfunction "1_1") (pintype "passive"))
      (node (ref "C22") (pin "1") (pinfunction "1_1") (pintype "passive"))
      (node (ref "C26") (pin "1") (pinfunction "1_1") (pintype "passive"))
      (node (ref "C28") (pin "1") (pinfunction "1_1") (pintype "passive"))
      (node (ref "C39") (pin "2") (pinfunction "2_2") (pintype "passive"))
      (node (ref "C4") (pin "1") (pinfunction "1_1") (pintype "passive"))
      (node (ref "C45") (pin "2") (pinfunction "2_2") (pintype "passive"))
      (node (ref "C7") (pin "1") (pinfunction "1_1") (pintype "passive"))
      (node (ref "C9") (pin "1") (pinfunction "1_1") (pintype "passive"))
      (node (ref "IC2") (pin "102") (pinfunction "__VCCINT_6_102") (pintype "power_in"))
      (node (ref "IC2") (pin "109") (pinfunction "__VCCD_PLL2_109") (pintype "power_in"))
      (node (ref "IC2") (pin "116") (pinfunction "__VCCINT_7_116") (pintype "power_in"))
      (node (ref "IC2") (pin "134") (pinfunction "__VCCINT_8_134") (pintype "power_in"))
      (node (ref "IC2") (pin "29") (pinfunction "__VCCINT_2_29") (pintype "power_in"))
      (node (ref "IC2") (pin "37") (pinfunction "__VCCD_PLL1_37") (pintype "power_in"))
      (node (ref "IC2") (pin "45") (pinfunction "__VCCINT_3_45") (pintype "power_in"))
      (node (ref "IC2") (pin "5") (pinfunction "__VCCINT_1_5") (pintype "power_in"))
      (node (ref "IC2") (pin "61") (pinfunction "__VCCINT_4_61") (pintype "power_in"))
      (node (ref "IC2") (pin "78") (pinfunction "__VCCINT_5_78") (pintype "power_in"))
      (node (ref "L1") (pin "P$2") (pinfunction "2_P$2") (pintype "passive"))
      (node (ref "R1") (pin "2") (pinfunction "2_2") (pintype "passive"))
      (node (ref "T+1V2") (pin "TP") (pinfunction "TP_TP") (pintype "input"))
      (node (ref "TP1") (pin "TP") (pinfunction "TP_TP") (pintype "input"))
    )
    (net (code "2") (name "+2V5") (class "Default")
      (node (ref "C27") (pin "1") (pinfunction "1_1") (pintype "passive"))
      (node (ref "C47") (pin "2") (pinfunction "2_2") (pintype "passive"))
      (node (ref "C8") (pin "1") (pinfunction "1_1") (pintype "passive"))
      (node (ref "IC2") (pin "107") (pinfunction "__VCCA2_107") (pintype "power_in"))
      (node (ref "IC2") (pin "35") (pinfunction "__VCCA1_35") (pintype "power_in"))
      (node (ref "IC8") (pin "5") (pinfunction "VOUT_5") (pintype "power_in"))
      (node (ref "T+2V5") (pin "TP") (pinfunction "TP_TP") (pintype "input"))
      (node (ref "TP3") (pin "TP") (pinfunction "TP_TP") (pintype "input"))
    )
    (net (code "3") (name "+3V3") (class "Default")
      (node (ref "C10") (pin "1") (pinfunction "1_1") (pintype "passive"))
      (node (ref "C11") (pin "1") (pinfunction "1_1") (pintype "passive"))
      (node (ref "C13") (pin "1") (pinfunction "1_1") (pintype "passive"))
      (node (ref "C15") (pin "1") (pinfunction "1_1") (pintype "passive"))
      (node (ref "C16") (pin "1") (pinfunction "1_1") (pintype "passive"))
      (node (ref "C17") (pin "1") (pinfunction "1_1") (pintype "passive"))
      (node (ref "C19") (pin "1") (pinfunction "1_1") (pintype "passive"))
      (node (ref "C20") (pin "1") (pinfunction "1_1") (pintype "passive"))
      (node (ref "C23") (pin "1") (pinfunction "1_1") (pintype "passive"))
      (node (ref "C24") (pin "1") (pinfunction "1_1") (pintype "passive"))
      (node (ref "C25") (pin "1") (pinfunction "1_1") (pintype "passive"))
      (node (ref "C29") (pin "1") (pinfunction "1_1") (pintype "passive"))
      (node (ref "C3") (pin "1") (pinfunction "1_1") (pintype "passive"))
      (node (ref "C30") (pin "1") (pinfunction "1_1") (pintype "passive"))
      (node (ref "C36") (pin "2") (pinfunction "2_2") (pintype "passive"))
      (node (ref "C37") (pin "1") (pinfunction "1_1") (pintype "passive"))
      (node (ref "C40") (pin "2") (pinfunction "2_2") (pintype "passive"))
      (node (ref "C41") (pin "1") (pinfunction "1_1") (pintype "passive"))
      (node (ref "C46") (pin "2") (pinfunction "2_2") (pintype "passive"))
      (node (ref "C48") (pin "2") (pinfunction "2_2") (pintype "passive"))
      (node (ref "C49") (pin "2") (pinfunction "2_2") (pintype "passive"))
      (node (ref "C5") (pin "1") (pinfunction "1_1") (pintype "passive"))
      (node (ref "C51") (pin "2") (pinfunction "2_2") (pintype "passive"))
      (node (ref "C52") (pin "1") (pinfunction "1_1") (pintype "passive"))
      (node (ref "C53") (pin "1") (pinfunction "1_1") (pintype "passive"))
      (node (ref "C56") (pin "1") (pinfunction "1_1") (pintype "passive"))
      (node (ref "C57") (pin "PLUS") (pinfunction "+_PLUS") (pintype "passive"))
      (node (ref "C6") (pin "1") (pinfunction "1_1") (pintype "passive"))
      (node (ref "C60") (pin "PLUS") (pinfunction "+_PLUS") (pintype "passive"))
      (node (ref "IC10") (pin "1") (pinfunction "DIR_1") (pintype "input"))
      (node (ref "IC10") (pin "20") (pinfunction "VCC_20") (pintype "power_in"))
      (node (ref "IC11") (pin "1") (pinfunction "DIR_1") (pintype "input"))
      (node (ref "IC11") (pin "20") (pinfunction "VCC_20") (pintype "power_in"))
      (node (ref "IC12") (pin "14") (pinfunction "VCC_14") (pintype "power_in"))
      (node (ref "IC13") (pin "14") (pinfunction "VCC_14") (pintype "power_in"))
      (node (ref "IC2") (pin "117") (pinfunction "__VCCIO7_1_117") (pintype "power_in"))
      (node (ref "IC2") (pin "122") (pinfunction "__VCCIO7_2_122") (pintype "power_in"))
      (node (ref "IC2") (pin "130") (pinfunction "__VCCIO8_1_130") (pintype "power_in"))
      (node (ref "IC2") (pin "139") (pinfunction "__VCCIO8_2_139") (pintype "power_in"))
      (node (ref "IC2") (pin "17") (pinfunction "__VCCIO1_17") (pintype "power_in"))
      (node (ref "IC2") (pin "26") (pinfunction "__VCCIO2_26") (pintype "power_in"))
      (node (ref "IC2") (pin "40") (pinfunction "__VCCIO3_1_40") (pintype "power_in"))
      (node (ref "IC2") (pin "47") (pinfunction "__VCCIO3_2_47") (pintype "power_in"))
      (node (ref "IC2") (pin "56") (pinfunction "__VCCIO4_1_56") (pintype "power_in"))
      (node (ref "IC2") (pin "62") (pinfunction "__VCCIO4_2_62") (pintype "power_in"))
      (node (ref "IC2") (pin "81") (pinfunction "__VCCIO5_81") (pintype "power_in"))
      (node (ref "IC2") (pin "93") (pinfunction "__VCCIO6_93") (pintype "power_in"))
      (node (ref "IC2") (pin "97") (pinfunction "__MSEL2_97") (pintype "bidirectional"))
      (node (ref "IC3") (pin "1") (pinfunction "DIR_1") (pintype "input"))
      (node (ref "IC3") (pin "20") (pinfunction "VCC_20") (pintype "power_in"))
      (node (ref "IC4") (pin "20") (pinfunction "VCC_20") (pintype "power_in"))
      (node (ref "IC7") (pin "5") (pinfunction "VCC_5") (pintype "power_in"))
      (node (ref "IC7") (pin "8") (pinfunction "V3_8") (pintype "passive"))
      (node (ref "IC8") (pin "3") (pinfunction "EN_3") (pintype "input"))
      (node (ref "IC9") (pin "8") (pinfunction "VCC_8") (pintype "power_in"))
      (node (ref "J1") (pin "4") (pinfunction "4_4") (pintype "passive"))
      (node (ref "J2") (pin "4") (pinfunction "VDD_4") (pintype "power_in"))
      (node (ref "L2") (pin "P$2") (pinfunction "2_P$2") (pintype "passive"))
      (node (ref "LED1") (pin "A") (pinfunction "A_A") (pintype "passive"))
      (node (ref "LED2") (pin "A") (pinfunction "A_A") (pintype "passive"))
      (node (ref "LED3") (pin "A") (pinfunction "A_A") (pintype "passive"))
      (node (ref "LED4") (pin "A") (pinfunction "A_A") (pintype "passive"))
      (node (ref "LED5") (pin "A") (pinfunction "A_A") (pintype "passive"))
      (node (ref "LED6") (pin "A") (pinfunction "A_A") (pintype "passive"))
      (node (ref "Q6") (pin "1") (pinfunction "S_1") (pintype "passive"))
      (node (ref "Q6") (pin "4") (pinfunction "S_4") (pintype "passive"))
      (node (ref "R13") (pin "1") (pinfunction "1_1") (pintype "passive"))
      (node (ref "R2") (pin "2") (pinfunction "2_2") (pintype "passive"))
      (node (ref "R20") (pin "2") (pinfunction "2_2") (pintype "passive"))
      (node (ref "R24") (pin "1") (pinfunction "1_1") (pintype "passive"))
      (node (ref "R27") (pin "2") (pinfunction "2_2") (pintype "passive"))
      (node (ref "R28") (pin "1") (pinfunction "1_1") (pintype "passive"))
      (node (ref "R3") (pin "2") (pinfunction "2_2") (pintype "passive"))
      (node (ref "R30") (pin "2") (pinfunction "2_2") (pintype "passive"))
      (node (ref "R31") (pin "2") (pinfunction "2_2") (pintype "passive"))
      (node (ref "R32") (pin "2") (pinfunction "2_2") (pintype "passive"))
      (node (ref "R34") (pin "2") (pinfunction "2_2") (pintype "passive"))
      (node (ref "R38") (pin "2") (pinfunction "2_2") (pintype "passive"))
      (node (ref "R4") (pin "2") (pinfunction "2_2") (pintype "passive"))
      (node (ref "R6") (pin "2") (pinfunction "2_2") (pintype "passive"))
      (node (ref "R7") (pin "2") (pinfunction "2_2") (pintype "passive"))
      (node (ref "R8") (pin "2") (pinfunction "2_2") (pintype "passive"))
      (node (ref "R9") (pin "2") (pinfunction "2_2") (pintype "passive"))
      (node (ref "T+3V3") (pin "TP") (pinfunction "TP_TP") (pintype "input"))
      (node (ref "U$1") (pin "1") (pinfunction "OE_1") (pintype "input"))
      (node (ref "U$1") (pin "4") (pinfunction "VCC_4") (pintype "power_in"))
      (node (ref "U$3") (pin "5") (pinfunction "VCC_5") (pintype "power_in"))
      (node (ref "U$5") (pin "B1") (pinfunction "+3V3_B1") (pintype "power_in"))
      (node (ref "U1") (pin "2") (pinfunction "3V3_2") (pintype "bidirectional"))
    )
    (net (code "4") (name "+5V") (class "Default")
      (node (ref "C33") (pin "2") (pinfunction "2_2") (pintype "passive"))
      (node (ref "CONN1") (pin "A3") (pinfunction "+5V_A3") (pintype "power_in"))
      (node (ref "IC1") (pin "5") (pinfunction "VIN_5") (pintype "power_in"))
      (node (ref "IC5") (pin "5") (pinfunction "VCC_5") (pintype "power_in"))
      (node (ref "IC8") (pin "1") (pinfunction "VIN_1") (pintype "power_in"))
      (node (ref "Q4") (pin "1") (pinfunction "S_1") (pintype "passive"))
      (node (ref "Q4") (pin "4") (pinfunction "S_4") (pintype "passive"))
      (node (ref "Q5") (pin "1") (pinfunction "S_1") (pintype "passive"))
      (node (ref "Q5") (pin "4") (pinfunction "S_4") (pintype "passive"))
      (node (ref "R11") (pin "2") (pinfunction "2_2") (pintype "passive"))
      (node (ref "R12") (pin "2") (pinfunction "2_2") (pintype "passive"))
      (node (ref "R25") (pin "1") (pinfunction "1_1") (pintype "passive"))
      (node (ref "R42") (pin "1") (pinfunction "1_1") (pintype "passive"))
      (node (ref "R5") (pin "1") (pinfunction "1_1") (pintype "passive"))
      (node (ref "R50") (pin "2") (pinfunction "2_2") (pintype "passive"))
      (node (ref "T+5V") (pin "TP") (pinfunction "TP_TP") (pintype "input"))
      (node (ref "U$5") (pin "A1") (pinfunction "+5V_A1") (pintype "power_in"))
    )
    (net (code "5") (name "+9V") (class "Default")
      (node (ref "CONN1") (pin "A4") (pinfunction "+9V_A4") (pintype "power_in"))
      (node (ref "R49") (pin "2") (pinfunction "2_2") (pintype "passive"))
      (node (ref "R53") (pin "2") (pinfunction "2_2") (pintype "passive"))
      (node (ref "T+9V") (pin "TP") (pinfunction "TP_TP") (pintype "input"))
      (node (ref "T2") (pin "4") (pinfunction "D_4") (pintype "passive"))
    )
    (net (code "6") (name "+12V") (class "Default")
      (node (ref "CONN1") (pin "B22") (pinfunction "+12V_B22") (pintype "power_in"))
      (node (ref "R47") (pin "2") (pinfunction "2_2") (pintype "passive"))
      (node (ref "T+12V") (pin "TP") (pinfunction "TP_TP") (pintype "input"))
      (node (ref "T2") (pin "5") (pinfunction "S_5") (pintype "passive"))
    )
    (net (code "7") (name "/-5V") (class "Default")
      (node (ref "CONN1") (pin "B20") (pinfunction "-5V_B20") (pintype "power_in"))
    )
    (net (code "8") (name "/-12V") (class "Default")
      (node (ref "CONN1") (pin "B23") (pinfunction "-12V_B23") (pintype "power_in"))
    )
    (net (code "9") (name "/2AROMCS") (class "Default")
      (node (ref "CONN1") (pin "A15") (pinfunction "VIDEO_A15") (pintype "bidirectional"))
      (node (ref "Q4") (pin "6") (pinfunction "D_6") (pintype "passive"))
    )
    (net (code "10") (name "/A0") (class "Default")
      (node (ref "CONN1") (pin "A9") (pinfunction "A0_A9") (pintype "bidirectional"))
      (node (ref "RN4") (pin "1") (pinfunction "1_1") (pintype "passive"))
    )
    (net (code "11") (name "/A1") (class "Default")
      (node (ref "CONN1") (pin "A10") (pinfunction "A1_A10") (pintype "bidirectional"))
      (node (ref "RN4") (pin "2") (pinfunction "1_2") (pintype "passive"))
    )
    (net (code "12") (name "/A2") (class "Default")
      (node (ref "CONN1") (pin "A11") (pinfunction "A2_A11") (pintype "bidirectional"))
      (node (ref "RN4") (pin "3") (pinfunction "1_3") (pintype "passive"))
    )
    (net (code "13") (name "/A3") (class "Default")
      (node (ref "CONN1") (pin "A12") (pinfunction "A3_A12") (pintype "bidirectional"))
      (node (ref "RN4") (pin "4") (pinfunction "1_4") (pintype "passive"))
    )
    (net (code "14") (name "/A4") (class "Default")
      (node (ref "CONN1") (pin "A24") (pinfunction "A4_A24") (pintype "bidirectional"))
      (node (ref "RN5") (pin "4") (pinfunction "1_4") (pintype "passive"))
    )
    (net (code "15") (name "/A5") (class "Default")
      (node (ref "CONN1") (pin "A23") (pinfunction "A5_A23") (pintype "bidirectional"))
      (node (ref "RN5") (pin "3") (pinfunction "1_3") (pintype "passive"))
    )
    (net (code "16") (name "/A6") (class "Default")
      (node (ref "CONN1") (pin "A22") (pinfunction "A6_A22") (pintype "bidirectional"))
      (node (ref "RN5") (pin "2") (pinfunction "1_2") (pintype "passive"))
    )
    (net (code "17") (name "/A7") (class "Default")
      (node (ref "CONN1") (pin "A21") (pinfunction "A7_A21") (pintype "bidirectional"))
      (node (ref "RN5") (pin "1") (pinfunction "1_1") (pintype "passive"))
    )
    (net (code "18") (name "/A8") (class "Default")
      (node (ref "CONN1") (pin "B26") (pinfunction "A8_B26") (pintype "bidirectional"))
      (node (ref "RN6") (pin "1") (pinfunction "1_1") (pintype "passive"))
    )
    (net (code "19") (name "/A9") (class "Default")
      (node (ref "CONN1") (pin "A27") (pinfunction "A9_A27") (pintype "bidirectional"))
      (node (ref "RN6") (pin "2") (pinfunction "1_2") (pintype "passive"))
    )
    (net (code "20") (name "/A10") (class "Default")
      (node (ref "CONN1") (pin "B27") (pinfunction "A10_B27") (pintype "bidirectional"))
      (node (ref "RN6") (pin "3") (pinfunction "1_3") (pintype "passive"))
    )
    (net (code "21") (name "/A11") (class "Default")
      (node (ref "CONN1") (pin "A28") (pinfunction "A11_A28") (pintype "bidirectional"))
      (node (ref "RN6") (pin "4") (pinfunction "1_4") (pintype "passive"))
    )
    (net (code "22") (name "/A12") (class "Default")
      (node (ref "CONN1") (pin "A2") (pinfunction "A12_A2") (pintype "bidirectional"))
      (node (ref "RN3") (pin "4") (pinfunction "1_4") (pintype "passive"))
    )
    (net (code "23") (name "/A13") (class "Default")
      (node (ref "CONN1") (pin "B2") (pinfunction "A13_B2") (pintype "bidirectional"))
      (node (ref "RN3") (pin "3") (pinfunction "1_3") (pintype "passive"))
    )
    (net (code "24") (name "/A14") (class "Default")
      (node (ref "CONN1") (pin "A1") (pinfunction "A14_A1") (pintype "bidirectional"))
      (node (ref "RN3") (pin "2") (pinfunction "1_2") (pintype "passive"))
    )
    (net (code "25") (name "/A15") (class "Default")
      (node (ref "CONN1") (pin "B1") (pinfunction "A15_B1") (pintype "bidirectional"))
      (node (ref "RN3") (pin "1") (pinfunction "1_1") (pintype "passive"))
    )
    (net (code "26") (name "/CK") (class "Default")
      (node (ref "CONN1") (pin "A8") (pinfunction "CK_A8") (pintype "bidirectional"))
      (node (ref "IC5") (pin "4") (pinfunction "O_4") (pintype "tri_state"))
      (node (ref "RN1") (pin "1") (pinfunction "1_1") (pintype "passive"))
    )
    (net (code "27") (name "/CK_OUT") (class "Default")
      (node (ref "IC2") (pin "112") (pinfunction "__IO_62_112") (pintype "bidirectional"))
      (node (ref "IC5") (pin "2") (pinfunction "I_2") (pintype "input"))
    )
    (net (code "28") (name "/CK_OUT_NEN") (class "Default")
      (node (ref "IC2") (pin "99") (pinfunction "__IO_53_99") (pintype "bidirectional"))
      (node (ref "IC5") (pin "1") (pinfunction "OE_1") (pintype "input"))
      (node (ref "R13") (pin "2") (pinfunction "2_2") (pintype "passive"))
    )
    (net (code "29") (name "/CONF_DONE") (class "Default")
      (node (ref "IC2") (pin "92") (pinfunction "__CONF_DONE_92") (pintype "bidirectional"))
      (node (ref "R27") (pin "1") (pinfunction "1_1") (pintype "passive"))
      (node (ref "U1") (pin "7") (pinfunction "IO35_7") (pintype "input"))
    )
    (net (code "30") (name "/D0") (class "Default")
      (node (ref "CONN1") (pin "B6") (pinfunction "D0_B6") (pintype "bidirectional"))
      (node (ref "RN7") (pin "2") (pinfunction "1_2") (pintype "passive"))
    )
    (net (code "31") (name "/D1") (class "Default")
      (node (ref "CONN1") (pin "B7") (pinfunction "D1_B7") (pintype "bidirectional"))
      (node (ref "RN7") (pin "3") (pinfunction "1_3") (pintype "passive"))
    )
    (net (code "32") (name "/D2") (class "Default")
      (node (ref "CONN1") (pin "B8") (pinfunction "D2_B8") (pintype "bidirectional"))
      (node (ref "RN7") (pin "4") (pinfunction "1_4") (pintype "passive"))
    )
    (net (code "33") (name "/D3") (class "Default")
      (node (ref "CONN1") (pin "B11") (pinfunction "D3_B11") (pintype "bidirectional"))
      (node (ref "RN8") (pin "3") (pinfunction "1_3") (pintype "passive"))
    )
    (net (code "34") (name "/D4") (class "Default")
      (node (ref "CONN1") (pin "B12") (pinfunction "D4_B12") (pintype "bidirectional"))
      (node (ref "RN8") (pin "4") (pinfunction "1_4") (pintype "passive"))
    )
    (net (code "35") (name "/D5") (class "Default")
      (node (ref "CONN1") (pin "B10") (pinfunction "D5_B10") (pintype "bidirectional"))
      (node (ref "RN8") (pin "2") (pinfunction "1_2") (pintype "passive"))
    )
    (net (code "36") (name "/D6") (class "Default")
      (node (ref "CONN1") (pin "B9") (pinfunction "D6_B9") (pintype "bidirectional"))
      (node (ref "RN8") (pin "1") (pinfunction "1_1") (pintype "passive"))
    )
    (net (code "37") (name "/D7") (class "Default")
      (node (ref "CONN1") (pin "B3") (pinfunction "D7_B3") (pintype "bidirectional"))
      (node (ref "RN7") (pin "1") (pinfunction "1_1") (pintype "passive"))
    )
    (net (code "38") (name "/DM") (class "Default")
      (node (ref "R36") (pin "2") (pinfunction "2_2") (pintype "passive"))
      (node (ref "R43") (pin "2") (pinfunction "2_2") (pintype "passive"))
      (node (ref "TV26") (pin "3") (pinfunction "B_3") (pintype "bidirectional"))
      (node (ref "USB2") (pin "D-") (pinfunction "D-_D-") (pintype "bidirectional"))
    )
    (net (code "39") (name "/DP") (class "Default")
      (node (ref "R35") (pin "2") (pinfunction "2_2") (pintype "passive"))
      (node (ref "R57") (pin "2") (pinfunction "2_2") (pintype "passive"))
      (node (ref "TV26") (pin "2") (pinfunction "A_2") (pintype "bidirectional"))
      (node (ref "USB2") (pin "D+") (pinfunction "D+_D+") (pintype "bidirectional"))
    )
    (net (code "40") (name "/D_BUS_DIR") (class "Default")
      (node (ref "IC2") (pin "11") (pinfunction "__IO_8_11") (pintype "bidirectional"))
      (node (ref "IC4") (pin "1") (pinfunction "DIR_1") (pintype "input"))
    )
    (net (code "41") (name "/D_BUS_OE") (class "Default")
      (node (ref "IC2") (pin "7") (pinfunction "__IO_5_7") (pintype "bidirectional"))
      (node (ref "IC4") (pin "19") (pinfunction "G_19") (pintype "input"))
      (node (ref "R24") (pin "2") (pinfunction "2_2") (pintype "passive"))
    )
    (net (code "42") (name "/ESP_EN") (class "Default")
      (node (ref "C1") (pin "2") (pinfunction "2_2") (pintype "passive"))
      (node (ref "R2") (pin "1") (pinfunction "1_1") (pintype "passive"))
      (node (ref "S1") (pin "B2") (pinfunction "2_B2") (pintype "passive"))
      (node (ref "U$3") (pin "1") (pinfunction "PA4_1") (pintype "passive"))
      (node (ref "U1") (pin "3") (pinfunction "EN_3") (pintype "bidirectional"))
    )
    (net (code "43") (name "/ESP_IO0") (class "Default")
      (node (ref "C2") (pin "2") (pinfunction "2_2") (pintype "passive"))
      (node (ref "R3") (pin "1") (pinfunction "1_1") (pintype "passive"))
      (node (ref "S2") (pin "B2") (pinfunction "2_B2") (pintype "passive"))
      (node (ref "U$3") (pin "3") (pinfunction "PA6_3") (pintype "passive"))
      (node (ref "U1") (pin "25") (pinfunction "IO0_25") (pintype "bidirectional"))
    )
    (net (code "44") (name "/ESP_IO26") (class "Default")
      (node (ref "IC2") (pin "138") (pinfunction "__IO_80_138") (pintype "bidirectional"))
      (node (ref "U1") (pin "11") (pinfunction "IO26_11") (pintype "bidirectional"))
    )
    (net (code "45") (name "/ESP_IO27") (class "Default")
      (node (ref "IC2") (pin "141") (pinfunction "__IO_81_141") (pintype "bidirectional"))
      (node (ref "U1") (pin "12") (pinfunction "IO27_12") (pintype "bidirectional"))
    )
    (net (code "46") (name "/ESP_MISO") (class "Default")
      (node (ref "IC2") (pin "6") (pinfunction "__IO_4/DATA/ADSO_6") (pintype "bidirectional"))
      (node (ref "U1") (pin "31") (pinfunction "IO19_31") (pintype "bidirectional"))
    )
    (net (code "47") (name "/ESP_MOSI") (class "Default")
      (node (ref "IC2") (pin "13") (pinfunction "__DATA0_13") (pintype "bidirectional"))
      (node (ref "U1") (pin "37") (pinfunction "IO23_37") (pintype "bidirectional"))
    )
    (net (code "48") (name "/ESP_NCS0") (class "Default")
      (node (ref "IC2") (pin "3") (pinfunction "__IO_3_3") (pintype "bidirectional"))
      (node (ref "U1") (pin "29") (pinfunction "IO5_29") (pintype "bidirectional"))
    )
    (net (code "49") (name "/ESP_QDH") (class "Default")
      (node (ref "IC2") (pin "1") (pinfunction "__IO_1_1") (pintype "bidirectional"))
      (node (ref "U1") (pin "33") (pinfunction "IO21_33") (pintype "bidirectional"))
    )
    (net (code "50") (name "/ESP_QWP") (class "Default")
      (node (ref "IC2") (pin "143") (pinfunction "__IO_83_143") (pintype "bidirectional"))
      (node (ref "U1") (pin "36") (pinfunction "IO22_36") (pintype "bidirectional"))
    )
    (net (code "51") (name "/ESP_RX") (class "Default")
      (node (ref "IC7") (pin "6") (pinfunction "TX_6") (pintype "output"))
      (node (ref "U$3") (pin "6") (pinfunction "PA3_6") (pintype "passive"))
      (node (ref "U1") (pin "34") (pinfunction "RXD0_34") (pintype "bidirectional"))
    )
    (net (code "52") (name "/ESP_SCK") (class "Default")
      (node (ref "IC2") (pin "12") (pinfunction "__DCLK_12") (pintype "input"))
      (node (ref "IC2") (pin "23") (pinfunction "__CLK1_23") (pintype "input"))
      (node (ref "U1") (pin "30") (pinfunction "IO18_30") (pintype "bidirectional"))
    )
    (net (code "53") (name "/ESP_TX") (class "Default")
      (node (ref "IC7") (pin "7") (pinfunction "RX_7") (pintype "input"))
      (node (ref "U1") (pin "35") (pinfunction "TXD0_35") (pintype "bidirectional"))
    )
    (net (code "54") (name "/EXT0") (class "Default")
      (node (ref "IC2") (pin "135") (pinfunction "__IO_77_135") (pintype "bidirectional"))
      (node (ref "U$5") (pin "B4") (pinfunction "E0_B4") (pintype "bidirectional"))
    )
    (net (code "55") (name "/EXT1") (class "Default")
      (node (ref "IC2") (pin "133") (pinfunction "__IO_76_133") (pintype "bidirectional"))
      (node (ref "U$5") (pin "B5") (pinfunction "E1_B5") (pintype "bidirectional"))
    )
    (net (code "56") (name "/EXT2") (class "Default")
      (node (ref "IC2") (pin "128") (pinfunction "__IO_73_128") (pintype "bidirectional"))
      (node (ref "U$5") (pin "B6") (pinfunction "E2_B6") (pintype "bidirectional"))
    )
    (net (code "57") (name "/EXT3") (class "Default")
      (node (ref "IC2") (pin "127") (pinfunction "__IO_72_127") (pintype "bidirectional"))
      (node (ref "U$5") (pin "B7") (pinfunction "E3_B7") (pintype "bidirectional"))
    )
    (net (code "58") (name "/EXT4") (class "Default")
      (node (ref "IC2") (pin "126") (pinfunction "__IO_71_126") (pintype "bidirectional"))
      (node (ref "U$5") (pin "B8") (pinfunction "E4_B8") (pintype "bidirectional"))
    )
    (net (code "59") (name "/EXT5") (class "Default")
      (node (ref "IC2") (pin "125") (pinfunction "__IO_70_125") (pintype "bidirectional"))
      (node (ref "U$5") (pin "B9") (pinfunction "E5_B9") (pintype "bidirectional"))
    )
    (net (code "60") (name "/EXT6") (class "Default")
      (node (ref "IC2") (pin "124") (pinfunction "__IO_69_124") (pintype "bidirectional"))
      (node (ref "U$5") (pin "B10") (pinfunction "E6_B10") (pintype "bidirectional"))
    )
    (net (code "61") (name "/EXT7") (class "Default")
      (node (ref "IC2") (pin "121") (pinfunction "__IO_68_121") (pintype "bidirectional"))
      (node (ref "U$5") (pin "A10") (pinfunction "E7_A10") (pintype "bidirectional"))
    )
    (net (code "62") (name "/EXT8") (class "Default")
      (node (ref "IC2") (pin "114") (pinfunction "__IO_64_114") (pintype "bidirectional"))
      (node (ref "U$5") (pin "A9") (pinfunction "E8_A9") (pintype "bidirectional"))
    )
    (net (code "63") (name "/EXT9") (class "Default")
      (node (ref "IC2") (pin "115") (pinfunction "__IO_65_115") (pintype "bidirectional"))
      (node (ref "U$5") (pin "A8") (pinfunction "E9_A8") (pintype "bidirectional"))
    )
    (net (code "64") (name "/EXT10") (class "Default")
      (node (ref "IC2") (pin "119") (pinfunction "__IO_66_119") (pintype "bidirectional"))
      (node (ref "U$5") (pin "A7") (pinfunction "E10_A7") (pintype "bidirectional"))
    )
    (net (code "65") (name "/EXT11") (class "Default")
      (node (ref "IC2") (pin "120") (pinfunction "__IO_67_120") (pintype "bidirectional"))
      (node (ref "U$5") (pin "A6") (pinfunction "E11_A6") (pintype "bidirectional"))
    )
    (net (code "66") (name "/EXT12") (class "Default")
      (node (ref "IC2") (pin "142") (pinfunction "__IO_82_142") (pintype "bidirectional"))
      (node (ref "U$5") (pin "A5") (pinfunction "E12_A5") (pintype "bidirectional"))
    )
    (net (code "67") (name "/EXT13") (class "Default")
      (node (ref "IC2") (pin "144") (pinfunction "__IO_84_144") (pintype "bidirectional"))
      (node (ref "U$5") (pin "A4") (pinfunction "E13_A4") (pintype "bidirectional"))
    )
    (net (code "68") (name "/FB2") (class "Default")
      (node (ref "IC6") (pin "4") (pinfunction "FB_4") (pintype "passive"))
      (node (ref "R18") (pin "2") (pinfunction "2_2") (pintype "passive"))
      (node (ref "R20") (pin "1") (pinfunction "1_1") (pintype "passive"))
    )
    (net (code "69") (name "/FLED0") (class "Default")
      (node (ref "IC2") (pin "76") (pinfunction "__IO_44_76") (pintype "bidirectional"))
      (node (ref "R41") (pin "2") (pinfunction "2_2") (pintype "passive"))
    )
    (net (code "70") (name "/FLED1") (class "Default")
      (node (ref "IC2") (pin "77") (pinfunction "__IO_45_77") (pintype "bidirectional"))
      (node (ref "R40") (pin "2") (pinfunction "2_2") (pintype "passive"))
    )
    (net (code "71") (name "/FLED2") (class "Default")
      (node (ref "IC2") (pin "80") (pinfunction "__IO_46_80") (pintype "bidirectional"))
      (node (ref "R39") (pin "2") (pinfunction "2_2") (pintype "passive"))
    )
    (net (code "72") (name "/FORCE_2AROMCS") (class "Default")
      (node (ref "IC13") (pin "5") (pinfunction "I_5") (pintype "input"))
      (node (ref "IC2") (pin "10") (pinfunction "__IO_7_10") (pintype "bidirectional"))
    )
    (net (code "73") (name "/FORCE_INT") (class "Default")
      (node (ref "IC13") (pin "1") (pinfunction "I_1") (pintype "input"))
      (node (ref "IC2") (pin "53") (pinfunction "__IO_26_53") (pintype "bidirectional"))
    )
    (net (code "74") (name "/FORCE_IORQULA") (class "Default")
      (node (ref "IC13") (pin "9") (pinfunction "I_9") (pintype "input"))
      (node (ref "IC2") (pin "136") (pinfunction "__IO_78_136") (pintype "bidirectional"))
    )
    (net (code "75") (name "/FORCE_NMI") (class "Default")
      (node (ref "IC13") (pin "3") (pinfunction "I_3") (pintype "input"))
      (node (ref "IC2") (pin "137") (pinfunction "__IO_79_137") (pintype "bidirectional"))
    )
    (net (code "76") (name "/FORCE_RESET") (class "Default")
      (node (ref "IC2") (pin "67") (pinfunction "__IO_35_67") (pintype "bidirectional"))
      (node (ref "Q1") (pin "1") (pinfunction "G_1") (pintype "passive"))
    )
    (net (code "77") (name "/FORCE_ROMCS") (class "Default")
      (node (ref "IC13") (pin "13") (pinfunction "I_13") (pintype "input"))
      (node (ref "IC2") (pin "132") (pinfunction "__IO_75_132") (pintype "bidirectional"))
    )
    (net (code "78") (name "/FORCE_WAIT") (class "Default")
      (node (ref "IC13") (pin "11") (pinfunction "I_11") (pintype "input"))
      (node (ref "IC2") (pin "129") (pinfunction "__IO_74_129") (pintype "bidirectional"))
    )
    (net (code "79") (name "/FR1") (class "Default")
      (node (ref "IC13") (pin "12") (pinfunction "O_12") (pintype "open_collector"))
      (node (ref "Q5") (pin "2") (pinfunction "G_2") (pintype "passive"))
      (node (ref "Q5") (pin "5") (pinfunction "G_5") (pintype "passive"))
      (node (ref "R5") (pin "2") (pinfunction "2_2") (pintype "passive"))
    )
    (net (code "80") (name "/FR2") (class "Default")
      (node (ref "IC13") (pin "8") (pinfunction "O_8") (pintype "open_collector"))
      (node (ref "Q4") (pin "5") (pinfunction "G_5") (pintype "passive"))
      (node (ref "R42") (pin "2") (pinfunction "2_2") (pintype "passive"))
    )
    (net (code "81") (name "/INT") (class "Default")
      (node (ref "CONN1") (pin "B13") (pinfunction "INT_B13") (pintype "bidirectional"))
      (node (ref "IC13") (pin "2") (pinfunction "O_2") (pintype "open_collector"))
      (node (ref "RN1") (pin "2") (pinfunction "1_2") (pintype "passive"))
    )
    (net (code "82") (name "/IO6") (class "Default")
      (node (ref "IC2") (pin "25") (pinfunction "__CLK3_25") (pintype "input"))
      (node (ref "U1") (pin "28") (pinfunction "IO17_28") (pintype "bidirectional"))
    )
    (net (code "83") (name "/IORQ") (class "Default")
      (node (ref "CONN1") (pin "B17") (pinfunction "IORQ_B17") (pintype "bidirectional"))
      (node (ref "RN1") (pin "4") (pinfunction "1_4") (pintype "passive"))
    )
    (net (code "84") (name "/IORQULA") (class "Default")
      (node (ref "CONN1") (pin "A13") (pinfunction "IORQULA_A13") (pintype "bidirectional"))
      (node (ref "Q4") (pin "3") (pinfunction "D_3") (pintype "passive"))
    )
    (net (code "85") (name "/LED1") (class "Default")
      (node (ref "R21") (pin "2") (pinfunction "2_2") (pintype "passive"))
      (node (ref "U1") (pin "8") (pinfunction "IO32_8") (pintype "bidirectional"))
    )
    (net (code "86") (name "/LED2") (class "Default")
      (node (ref "IC2") (pin "2") (pinfunction "__IO_2_2") (pintype "bidirectional"))
      (node (ref "R22") (pin "2") (pinfunction "2_2") (pintype "passive"))
    )
    (net (code "87") (name "/M1") (class "Default")
      (node (ref "CONN1") (pin "B24") (pinfunction "M1_B24") (pintype "bidirectional"))
      (node (ref "RN2") (pin "3") (pinfunction "1_3") (pintype "passive"))
    )
    (net (code "88") (name "/MREQ") (class "Default")
      (node (ref "CONN1") (pin "B16") (pinfunction "MREQ_B16") (pintype "bidirectional"))
      (node (ref "RN1") (pin "3") (pinfunction "1_3") (pintype "passive"))
    )
    (net (code "89") (name "/NCONFIG") (class "Default")
      (node (ref "IC2") (pin "14") (pinfunction "__NCONFIG_14") (pintype "bidirectional"))
      (node (ref "R7") (pin "1") (pinfunction "1_1") (pintype "passive"))
      (node (ref "U1") (pin "10") (pinfunction "IO25_10") (pintype "bidirectional"))
    )
    (net (code "90") (name "/NMI") (class "Default")
      (node (ref "CONN1") (pin "B14") (pinfunction "NMI_B14") (pintype "bidirectional"))
      (node (ref "IC13") (pin "4") (pinfunction "O_4") (pintype "open_collector"))
    )
    (net (code "91") (name "/NSTATUS") (class "Default")
      (node (ref "IC2") (pin "9") (pinfunction "__NSTATUS_9") (pintype "bidirectional"))
      (node (ref "R6") (pin "1") (pinfunction "1_1") (pintype "passive"))
      (node (ref "U1") (pin "27") (pinfunction "IO16_27") (pintype "bidirectional"))
    )
    (net (code "92") (name "/PEN1") (class "Default")
      (node (ref "IC1") (pin "4") (pinfunction "NEN_4") (pintype "input"))
      (node (ref "R37") (pin "1") (pinfunction "1_1") (pintype "passive"))
    )
    (net (code "93") (name "/PULLUP_EN") (class "Default")
      (node (ref "Q6") (pin "2") (pinfunction "G_2") (pintype "passive"))
      (node (ref "Q6") (pin "5") (pinfunction "G_5") (pintype "passive"))
      (node (ref "R28") (pin "2") (pinfunction "2_2") (pintype "passive"))
      (node (ref "U1") (pin "9") (pinfunction "IO33_9") (pintype "bidirectional"))
    )
    (net (code "94") (name "/RAMCLK") (class "Default")
      (node (ref "IC2") (pin "84") (pinfunction "__IO_48_84") (pintype "bidirectional"))
      (node (ref "IC9") (pin "6") (pinfunction "SCK_6") (pintype "input"))
    )
    (net (code "95") (name "/RAMD0") (class "Default")
      (node (ref "IC2") (pin "83") (pinfunction "__IO_47_83") (pintype "bidirectional"))
      (node (ref "IC9") (pin "5") (pinfunction "SI/SIO[0]_5") (pintype "bidirectional"))
    )
    (net (code "96") (name "/RAMD1") (class "Default")
      (node (ref "IC2") (pin "87") (pinfunction "__IO_51_87") (pintype "bidirectional"))
      (node (ref "IC9") (pin "2") (pinfunction "SO/SIO[1]_2") (pintype "bidirectional"))
    )
    (net (code "97") (name "/RAMD2") (class "Default")
      (node (ref "IC2") (pin "86") (pinfunction "__IO_50_86") (pintype "bidirectional"))
      (node (ref "IC9") (pin "3") (pinfunction "SIO[2]_3") (pintype "bidirectional"))
    )
    (net (code "98") (name "/RAMD3") (class "Default")
      (node (ref "IC2") (pin "85") (pinfunction "__IO_49_85") (pintype "bidirectional"))
      (node (ref "IC9") (pin "7") (pinfunction "SIO[3]_7") (pintype "bidirectional"))
    )
    (net (code "99") (name "/RAMNCS") (class "Default")
      (node (ref "IC2") (pin "98") (pinfunction "__IO_52_98") (pintype "bidirectional"))
      (node (ref "IC9") (pin "1") (pinfunction "NCS_1") (pintype "input"))
    )
    (net (code "100") (name "/RCV") (class "Default")
      (node (ref "IC12") (pin "3") (pinfunction "RCV_3") (pintype "output"))
      (node (ref "IC2") (pin "103") (pinfunction "__IO_56_103") (pintype "bidirectional"))
    )
    (net (code "101") (name "/RD") (class "Default")
      (node (ref "CONN1") (pin "B18") (pinfunction "RD_B18") (pintype "bidirectional"))
      (node (ref "RN2") (pin "1") (pinfunction "1_1") (pintype "passive"))
    )
    (net (code "102") (name "/RESET") (class "Default")
      (node (ref "CONN1") (pin "A20") (pinfunction "RESET_A20") (pintype "bidirectional"))
      (node (ref "Q1") (pin "3") (pinfunction "D_3") (pintype "passive"))
    )
    (net (code "103") (name "/RFSH") (class "Default")
      (node (ref "CONN1") (pin "B25") (pinfunction "RFSH_B25") (pintype "bidirectional"))
      (node (ref "RN2") (pin "4") (pinfunction "1_4") (pintype "passive"))
    )
    (net (code "104") (name "/ROMCS") (class "Default")
      (node (ref "CONN1") (pin "A25") (pinfunction "ROMCS_A25") (pintype "bidirectional"))
      (node (ref "Q5") (pin "6") (pinfunction "D_6") (pintype "passive"))
    )
    (net (code "105") (name "/ROMCS2") (class "Default")
      (node (ref "CONN1") (pin "B4") (pinfunction "NC3_B4") (pintype "passive"))
      (node (ref "R14") (pin "1") (pinfunction "1_1") (pintype "passive"))
    )
    (net (code "106") (name "/RTS") (class "Default")
      (node (ref "IC7") (pin "4") (pinfunction "RTS_4") (pintype "output"))
      (node (ref "U$3") (pin "4") (pinfunction "PA5_4") (pintype "passive"))
    )
    (net (code "107") (name "/SDMMC_CK") (class "Default")
      (node (ref "J2") (pin "5") (pinfunction "CLK_5") (pintype "passive"))
      (node (ref "R32") (pin "1") (pinfunction "1_1") (pintype "passive"))
      (node (ref "U1") (pin "13") (pinfunction "IO14_13") (pintype "bidirectional"))
    )
    (net (code "108") (name "/SDMMC_CMD") (class "Default")
      (node (ref "J2") (pin "3") (pinfunction "CMD_3") (pintype "passive"))
      (node (ref "R31") (pin "1") (pinfunction "1_1") (pintype "passive"))
      (node (ref "U1") (pin "23") (pinfunction "IO15_23") (pintype "bidirectional"))
    )
    (net (code "109") (name "/SDMMC_D0") (class "Default")
      (node (ref "J2") (pin "7") (pinfunction "DAT0_7") (pintype "passive"))
      (node (ref "R33") (pin "2") (pinfunction "2_2") (pintype "passive"))
      (node (ref "U1") (pin "24") (pinfunction "IO2_24") (pintype "bidirectional"))
    )
    (net (code "110") (name "/SDMMC_D1") (class "Default")
      (node (ref "J2") (pin "8") (pinfunction "DAT1_8") (pintype "passive"))
      (node (ref "R34") (pin "1") (pinfunction "1_1") (pintype "passive"))
      (node (ref "U1") (pin "26") (pinfunction "IO4_26") (pintype "bidirectional"))
    )
    (net (code "111") (name "/SDMMC_D2") (class "Default")
      (node (ref "J2") (pin "1") (pinfunction "DAT2_1") (pintype "passive"))
      (node (ref "R29") (pin "2") (pinfunction "2_2") (pintype "passive"))
      (node (ref "U1") (pin "14") (pinfunction "IO12_14") (pintype "bidirectional"))
    )
    (net (code "112") (name "/SDMMC_D3") (class "Default")
      (node (ref "J2") (pin "2") (pinfunction "CD/DAT3^2_2") (pintype "passive"))
      (node (ref "R30") (pin "1") (pinfunction "1_1") (pintype "passive"))
      (node (ref "U1") (pin "16") (pinfunction "IO13_16") (pintype "bidirectional"))
    )
    (net (code "113") (name "/SW1") (class "Default")
      (node (ref "C42") (pin "1") (pinfunction "1_1") (pintype "passive"))
      (node (ref "IC14") (pin "2") (pinfunction "SW_2") (pintype "passive"))
      (node (ref "L1") (pin "P$1") (pinfunction "1_P$1") (pintype "passive"))
    )
    (net (code "114") (name "/SW2") (class "Default")
      (node (ref "C43") (pin "1") (pinfunction "1_1") (pintype "passive"))
      (node (ref "IC6") (pin "2") (pinfunction "SW_2") (pintype "passive"))
      (node (ref "L2") (pin "P$1") (pinfunction "1_P$1") (pintype "passive"))
    )
    (net (code "115") (name "/SWITCH") (class "Default")
      (node (ref "R4") (pin "1") (pinfunction "1_1") (pintype "passive"))
      (node (ref "S3") (pin "B2") (pinfunction "2_B2") (pintype "passive"))
      (node (ref "U1") (pin "6") (pinfunction "IO34_6") (pintype "input"))
    )
    (net (code "116") (name "/TCK") (class "Default")
      (node (ref "IC2") (pin "16") (pinfunction "__TCK_16") (pintype "bidirectional"))
      (node (ref "J1") (pin "1") (pinfunction "1_1") (pintype "passive"))
      (node (ref "R10") (pin "1") (pinfunction "1_1") (pintype "passive"))
    )
    (net (code "117") (name "/TDI") (class "Default")
      (node (ref "IC2") (pin "15") (pinfunction "__TDI_15") (pintype "bidirectional"))
      (node (ref "J1") (pin "9") (pinfunction "9_9") (pintype "passive"))
    )
    (net (code "118") (name "/TDO") (class "Default")
      (node (ref "IC2") (pin "20") (pinfunction "__TDO_20") (pintype "bidirectional"))
      (node (ref "J1") (pin "3") (pinfunction "3_3") (pintype "passive"))
      (node (ref "R8") (pin "1") (pinfunction "1_1") (pintype "passive"))
    )
    (net (code "119") (name "/TMS") (class "Default")
      (node (ref "IC2") (pin "18") (pinfunction "__TMS_18") (pintype "bidirectional"))
      (node (ref "J1") (pin "5") (pinfunction "5_5") (pintype "passive"))
      (node (ref "R9") (pin "1") (pinfunction "1_1") (pintype "passive"))
    )
    (net (code "120") (name "/USB_FLT") (class "Default")
      (node (ref "IC1") (pin "3") (pinfunction "FAULT_3") (pintype "output"))
      (node (ref "IC2") (pin "91") (pinfunction "__CLK4_91") (pintype "input"))
      (node (ref "R38") (pin "1") (pinfunction "1_1") (pintype "passive"))
    )
    (net (code "121") (name "/USB_MODE") (class "Default")
      (node (ref "IC12") (pin "1") (pinfunction "MODE_1") (pintype "input"))
      (node (ref "IC2") (pin "105") (pinfunction "__IO_58_105") (pintype "bidirectional"))
    )
    (net (code "122") (name "/USB_OE") (class "Default")
      (node (ref "IC12") (pin "2") (pinfunction "OE_2") (pintype "input"))
      (node (ref "IC2") (pin "104") (pinfunction "__IO_57_104") (pintype "bidirectional"))
    )
    (net (code "123") (name "/USB_PWREN") (class "Default")
      (node (ref "IC2") (pin "113") (pinfunction "__IO_63_113") (pintype "bidirectional"))
      (node (ref "R37") (pin "2") (pinfunction "2_2") (pintype "passive"))
    )
    (net (code "124") (name "/USB_SPEED") (class "Default")
      (node (ref "IC12") (pin "9") (pinfunction "SPEED_9") (pintype "input"))
      (node (ref "IC2") (pin "106") (pinfunction "__IO_59_106") (pintype "bidirectional"))
    )
    (net (code "125") (name "/VBUS") (class "Default")
      (node (ref "C59") (pin "+") (pinfunction "+_+") (pintype "passive"))
      (node (ref "IC1") (pin "1") (pinfunction "VOUT_1") (pintype "power_in"))
      (node (ref "TV26") (pin "4") (pinfunction "C_4") (pintype "bidirectional"))
      (node (ref "USB2") (pin "VBUS") (pinfunction "VBUS_VBUS") (pintype "bidirectional"))
    )
    (net (code "126") (name "/VM") (class "Default")
      (node (ref "IC12") (pin "5") (pinfunction "VM_5") (pintype "output"))
      (node (ref "IC2") (pin "100") (pinfunction "__IO_54_100") (pintype "bidirectional"))
    )
    (net (code "127") (name "/VMO") (class "Default")
      (node (ref "IC12") (pin "13") (pinfunction "VMO_13") (pintype "input"))
      (node (ref "IC2") (pin "111") (pinfunction "__IO_61_111") (pintype "bidirectional"))
    )
    (net (code "128") (name "/VP") (class "Default")
      (node (ref "IC12") (pin "4") (pinfunction "VP_4") (pintype "output"))
      (node (ref "IC2") (pin "101") (pinfunction "__IO_55_101") (pintype "bidirectional"))
    )
    (net (code "129") (name "/VPO") (class "Default")
      (node (ref "IC12") (pin "12") (pinfunction "VPO_12") (pintype "input"))
      (node (ref "IC2") (pin "110") (pinfunction "__IO_60_110") (pintype "bidirectional"))
    )
    (net (code "130") (name "/VSENS") (class "Default")
      (node (ref "R46") (pin "1") (pinfunction "1_1") (pintype "passive"))
      (node (ref "U1") (pin "4") (pinfunction "SENSOR_VP_4") (pintype "input"))
    )
    (net (code "131") (name "/VSWITCH") (class "Default")
      (node (ref "C31") (pin "2") (pinfunction "2_2") (pintype "passive"))
      (node (ref "C32") (pin "2") (pinfunction "2_2") (pintype "passive"))
      (node (ref "C34") (pin "2") (pinfunction "2_2") (pintype "passive"))
      (node (ref "C54") (pin "2") (pinfunction "2_2") (pintype "passive"))
      (node (ref "IC14") (pin "3") (pinfunction "VIN_3") (pintype "power_in"))
      (node (ref "IC6") (pin "3") (pinfunction "VIN_3") (pintype "power_in"))
      (node (ref "R44") (pin "2") (pinfunction "2_2") (pintype "passive"))
      (node (ref "R51") (pin "2") (pinfunction "2_2") (pintype "passive"))
      (node (ref "T2") (pin "2") (pinfunction "S_2") (pintype "passive"))
      (node (ref "T2") (pin "6") (pinfunction "D_6") (pintype "passive"))
      (node (ref "TP5") (pin "TP") (pinfunction "TP_TP") (pintype "input"))
    )
    (net (code "132") (name "/WAIT") (class "Default")
      (node (ref "CONN1") (pin "B21") (pinfunction "WAIT_B21") (pintype "bidirectional"))
      (node (ref "IC13") (pin "10") (pinfunction "O_10") (pintype "open_collector"))
    )
    (net (code "133") (name "/WR") (class "Default")
      (node (ref "CONN1") (pin "B19") (pinfunction "WR_B19") (pintype "bidirectional"))
      (node (ref "RN2") (pin "2") (pinfunction "1_2") (pintype "passive"))
    )
    (net (code "134") (name "/XCK") (class "Default")
      (node (ref "IC2") (pin "54") (pinfunction "__IO_27_54") (pintype "bidirectional"))
      (node (ref "IC3") (pin "18") (pinfunction "B1_18") (pintype "bidirectional"))
    )
    (net (code "135") (name "/XD0") (class "Default")
      (node (ref "IC2") (pin "43") (pinfunction "__IO_19_43") (pintype "bidirectional"))
      (node (ref "IC4") (pin "17") (pinfunction "B2_17") (pintype "bidirectional"))
    )
    (net (code "136") (name "/XD1") (class "Default")
      (node (ref "IC2") (pin "44") (pinfunction "__IO_20_44") (pintype "bidirectional"))
      (node (ref "IC4") (pin "16") (pinfunction "B3_16") (pintype "bidirectional"))
    )
    (net (code "137") (name "/XD2") (class "Default")
      (node (ref "IC2") (pin "46") (pinfunction "__IO_21_46") (pintype "bidirectional"))
      (node (ref "IC4") (pin "15") (pinfunction "B4_15") (pintype "bidirectional"))
    )
    (net (code "138") (name "/XD3") (class "Default")
      (node (ref "IC2") (pin "51") (pinfunction "__IO_24_51") (pintype "bidirectional"))
      (node (ref "IC4") (pin "12") (pinfunction "B7_12") (pintype "bidirectional"))
    )
    (net (code "139") (name "/XD4") (class "Default")
      (node (ref "IC2") (pin "52") (pinfunction "__IO_25_52") (pintype "bidirectional"))
      (node (ref "IC4") (pin "11") (pinfunction "B8_11") (pintype "bidirectional"))
    )
    (net (code "140") (name "/XD5") (class "Default")
      (node (ref "IC2") (pin "50") (pinfunction "__IO_23_50") (pintype "bidirectional"))
      (node (ref "IC4") (pin "13") (pinfunction "B6_13") (pintype "bidirectional"))
    )
    (net (code "141") (name "/XD6") (class "Default")
      (node (ref "IC2") (pin "49") (pinfunction "__IO_22_49") (pintype "bidirectional"))
      (node (ref "IC4") (pin "14") (pinfunction "B5_14") (pintype "bidirectional"))
    )
    (net (code "142") (name "/XD7") (class "Default")
      (node (ref "IC2") (pin "42") (pinfunction "__IO_18_42") (pintype "bidirectional"))
      (node (ref "IC4") (pin "18") (pinfunction "B1_18") (pintype "bidirectional"))
    )
    (net (code "143") (name "/XINT") (class "Default")
      (node (ref "IC2") (pin "55") (pinfunction "__IO_28_55") (pintype "bidirectional"))
      (node (ref "IC3") (pin "17") (pinfunction "B2_17") (pintype "bidirectional"))
    )
    (net (code "144") (name "/XIORQ") (class "Default")
      (node (ref "IC2") (pin "59") (pinfunction "__IO_30_59") (pintype "bidirectional"))
      (node (ref "IC3") (pin "15") (pinfunction "B4_15") (pintype "bidirectional"))
    )
    (net (code "145") (name "/XM1") (class "Default")
      (node (ref "IC2") (pin "65") (pinfunction "__IO_33_65") (pintype "bidirectional"))
      (node (ref "IC3") (pin "12") (pinfunction "B7_12") (pintype "bidirectional"))
    )
    (net (code "146") (name "/XMREQ") (class "Default")
      (node (ref "IC2") (pin "58") (pinfunction "__IO_29_58") (pintype "bidirectional"))
      (node (ref "IC3") (pin "16") (pinfunction "B3_16") (pintype "bidirectional"))
    )
    (net (code "147") (name "/XRD") (class "Default")
      (node (ref "IC2") (pin "60") (pinfunction "__IO_31_60") (pintype "bidirectional"))
      (node (ref "IC3") (pin "14") (pinfunction "B5_14") (pintype "bidirectional"))
    )
    (net (code "148") (name "/XRFSH") (class "Default")
      (node (ref "IC2") (pin "66") (pinfunction "__IO_34_66") (pintype "bidirectional"))
      (node (ref "IC3") (pin "11") (pinfunction "B8_11") (pintype "bidirectional"))
    )
    (net (code "149") (name "/XWR") (class "Default")
      (node (ref "IC2") (pin "64") (pinfunction "__IO_32_64") (pintype "bidirectional"))
      (node (ref "IC3") (pin "13") (pinfunction "B6_13") (pintype "bidirectional"))
    )
    (net (code "150") (name "/ZX_A0") (class "Default")
      (node (ref "IC10") (pin "14") (pinfunction "B5_14") (pintype "bidirectional"))
      (node (ref "IC2") (pin "33") (pinfunction "__IO_14_33") (pintype "bidirectional"))
    )
    (net (code "151") (name "/ZX_A1") (class "Default")
      (node (ref "IC10") (pin "13") (pinfunction "B6_13") (pintype "bidirectional"))
      (node (ref "IC2") (pin "34") (pinfunction "__IO_15_34") (pintype "bidirectional"))
    )
    (net (code "152") (name "/ZX_A2") (class "Default")
      (node (ref "IC10") (pin "12") (pinfunction "B7_12") (pintype "bidirectional"))
      (node (ref "IC2") (pin "38") (pinfunction "__IO_16_38") (pintype "bidirectional"))
    )
    (net (code "153") (name "/ZX_A3") (class "Default")
      (node (ref "IC10") (pin "11") (pinfunction "B8_11") (pintype "bidirectional"))
      (node (ref "IC2") (pin "39") (pinfunction "__IO_17_39") (pintype "bidirectional"))
    )
    (net (code "154") (name "/ZX_A4") (class "Default")
      (node (ref "IC11") (pin "15") (pinfunction "B4_15") (pintype "bidirectional"))
      (node (ref "IC2") (pin "71") (pinfunction "__IO_39_71") (pintype "bidirectional"))
    )
    (net (code "155") (name "/ZX_A5") (class "Default")
      (node (ref "IC11") (pin "16") (pinfunction "B3_16") (pintype "bidirectional"))
      (node (ref "IC2") (pin "70") (pinfunction "__IO_38_70") (pintype "bidirectional"))
    )
    (net (code "156") (name "/ZX_A6") (class "Default")
      (node (ref "IC11") (pin "17") (pinfunction "B2_17") (pintype "bidirectional"))
      (node (ref "IC2") (pin "69") (pinfunction "__IO_37_69") (pintype "bidirectional"))
    )
    (net (code "157") (name "/ZX_A7") (class "Default")
      (node (ref "IC11") (pin "18") (pinfunction "B1_18") (pintype "bidirectional"))
      (node (ref "IC2") (pin "68") (pinfunction "__IO_36_68") (pintype "bidirectional"))
    )
    (net (code "158") (name "/ZX_A8") (class "Default")
      (node (ref "IC11") (pin "14") (pinfunction "B5_14") (pintype "bidirectional"))
      (node (ref "IC2") (pin "72") (pinfunction "__IO_40_72") (pintype "bidirectional"))
    )
    (net (code "159") (name "/ZX_A9") (class "Default")
      (node (ref "IC11") (pin "13") (pinfunction "B6_13") (pintype "bidirectional"))
      (node (ref "IC2") (pin "73") (pinfunction "__IO_41_73") (pintype "bidirectional"))
    )
    (net (code "160") (name "/ZX_A10") (class "Default")
      (node (ref "IC11") (pin "12") (pinfunction "B7_12") (pintype "bidirectional"))
      (node (ref "IC2") (pin "74") (pinfunction "__IO_42_74") (pintype "bidirectional"))
    )
    (net (code "161") (name "/ZX_A11") (class "Default")
      (node (ref "IC11") (pin "11") (pinfunction "B8_11") (pintype "bidirectional"))
      (node (ref "IC2") (pin "75") (pinfunction "__IO_43_75") (pintype "bidirectional"))
    )
    (net (code "162") (name "/ZX_A12") (class "Default")
      (node (ref "IC10") (pin "15") (pinfunction "B4_15") (pintype "bidirectional"))
      (node (ref "IC2") (pin "32") (pinfunction "__IO_13_32") (pintype "bidirectional"))
    )
    (net (code "163") (name "/ZX_A13") (class "Default")
      (node (ref "IC10") (pin "16") (pinfunction "B3_16") (pintype "bidirectional"))
      (node (ref "IC2") (pin "31") (pinfunction "__IO_12_31") (pintype "bidirectional"))
    )
    (net (code "164") (name "/ZX_A14") (class "Default")
      (node (ref "IC10") (pin "17") (pinfunction "B2_17") (pintype "bidirectional"))
      (node (ref "IC2") (pin "30") (pinfunction "__IO_11_30") (pintype "bidirectional"))
    )
    (net (code "165") (name "/ZX_A15") (class "Default")
      (node (ref "IC10") (pin "18") (pinfunction "B1_18") (pintype "bidirectional"))
      (node (ref "IC2") (pin "28") (pinfunction "__IO_10_28") (pintype "bidirectional"))
    )
    (net (code "166") (name "GND") (class "Default")
      (node (ref "C1") (pin "1") (pinfunction "1_1") (pintype "passive"))
      (node (ref "C10") (pin "2") (pinfunction "2_2") (pintype "passive"))
      (node (ref "C11") (pin "2") (pinfunction "2_2") (pintype "passive"))
      (node (ref "C12") (pin "2") (pinfunction "2_2") (pintype "passive"))
      (node (ref "C13") (pin "2") (pinfunction "2_2") (pintype "passive"))
      (node (ref "C14") (pin "2") (pinfunction "2_2") (pintype "passive"))
      (node (ref "C15") (pin "2") (pinfunction "2_2") (pintype "passive"))
      (node (ref "C16") (pin "2") (pinfunction "2_2") (pintype "passive"))
      (node (ref "C17") (pin "2") (pinfunction "2_2") (pintype "passive"))
      (node (ref "C18") (pin "2") (pinfunction "2_2") (pintype "passive"))
      (node (ref "C19") (pin "2") (pinfunction "2_2") (pintype "passive"))
      (node (ref "C2") (pin "1") (pinfunction "1_1") (pintype "passive"))
      (node (ref "C20") (pin "2") (pinfunction "2_2") (pintype "passive"))
      (node (ref "C21") (pin "2") (pinfunction "2_2") (pintype "passive"))
      (node (ref "C22") (pin "2") (pinfunction "2_2") (pintype "passive"))
      (node (ref "C23") (pin "2") (pinfunction "2_2") (pintype "passive"))
      (node (ref "C24") (pin "2") (pinfunction "2_2") (pintype "passive"))
      (node (ref "C25") (pin "2") (pinfunction "2_2") (pintype "passive"))
      (node (ref "C26") (pin "2") (pinfunction "2_2") (pintype "passive"))
      (node (ref "C27") (pin "2") (pinfunction "2_2") (pintype "passive"))
      (node (ref "C28") (pin "2") (pinfunction "2_2") (pintype "passive"))
      (node (ref "C29") (pin "2") (pinfunction "2_2") (pintype "passive"))
      (node (ref "C3") (pin "2") (pinfunction "2_2") (pintype "passive"))
      (node (ref "C30") (pin "2") (pinfunction "2_2") (pintype "passive"))
      (node (ref "C31") (pin "1") (pinfunction "1_1") (pintype "passive"))
      (node (ref "C32") (pin "1") (pinfunction "1_1") (pintype "passive"))
      (node (ref "C33") (pin "1") (pinfunction "1_1") (pintype "passive"))
      (node (ref "C34") (pin "1") (pinfunction "1_1") (pintype "passive"))
      (node (ref "C36") (pin "1") (pinfunction "1_1") (pintype "passive"))
      (node (ref "C37") (pin "2") (pinfunction "2_2") (pintype "passive"))
      (node (ref "C39") (pin "1") (pinfunction "1_1") (pintype "passive"))
      (node (ref "C4") (pin "2") (pinfunction "2_2") (pintype "passive"))
      (node (ref "C40") (pin "1") (pinfunction "1_1") (pintype "passive"))
      (node (ref "C41") (pin "2") (pinfunction "2_2") (pintype "passive"))
      (node (ref "C45") (pin "1") (pinfunction "1_1") (pintype "passive"))
      (node (ref "C46") (pin "1") (pinfunction "1_1") (pintype "passive"))
      (node (ref "C47") (pin "1") (pinfunction "1_1") (pintype "passive"))
      (node (ref "C48") (pin "1") (pinfunction "1_1") (pintype "passive"))
      (node (ref "C49") (pin "1") (pinfunction "1_1") (pintype "passive"))
      (node (ref "C5") (pin "2") (pinfunction "2_2") (pintype "passive"))
      (node (ref "C50") (pin "2") (pinfunction "2_2") (pintype "passive"))
      (node (ref "C51") (pin "1") (pinfunction "1_1") (pintype "passive"))
      (node (ref "C52") (pin "2") (pinfunction "2_2") (pintype "passive"))
      (node (ref "C53") (pin "2") (pinfunction "2_2") (pintype "passive"))
      (node (ref "C56") (pin "2") (pinfunction "2_2") (pintype "passive"))
      (node (ref "C57") (pin "MINUS") (pinfunction "-_MINUS") (pintype "passive"))
      (node (ref "C59") (pin "-") (pinfunction "-_-") (pintype "passive"))
      (node (ref "C6") (pin "2") (pinfunction "2_2") (pintype "passive"))
      (node (ref "C60") (pin "MINUS") (pinfunction "-_MINUS") (pintype "passive"))
      (node (ref "C7") (pin "2") (pinfunction "2_2") (pintype "passive"))
      (node (ref "C8") (pin "2") (pinfunction "2_2") (pintype "passive"))
      (node (ref "C9") (pin "2") (pinfunction "2_2") (pintype "passive"))
      (node (ref "CONN1") (pin "A14") (pinfunction "GND_A14") (pintype "power_in"))
      (node (ref "CONN1") (pin "A6") (pinfunction "GND_A6") (pintype "power_in"))
      (node (ref "CONN1") (pin "A7") (pinfunction "GND_A7") (pintype "power_in"))
      (node (ref "IC1") (pin "2") (pinfunction "GND_2") (pintype "power_in"))
      (node (ref "IC10") (pin "10") (pinfunction "GND_10") (pintype "power_in"))
      (node (ref "IC10") (pin "19") (pinfunction "G_19") (pintype "input"))
      (node (ref "IC11") (pin "10") (pinfunction "GND_10") (pintype "power_in"))
      (node (ref "IC11") (pin "19") (pinfunction "G_19") (pintype "input"))
      (node (ref "IC12") (pin "6") (pinfunction "SUSPND_6") (pintype "input"))
      (node (ref "IC12") (pin "7") (pinfunction "GND_7") (pintype "power_in"))
      (node (ref "IC13") (pin "7") (pinfunction "GND_7") (pintype "power_in"))
      (node (ref "IC14") (pin "1") (pinfunction "GND_1") (pintype "power_in"))
      (node (ref "IC2") (pin "108") (pinfunction "__GNDA2_108") (pintype "power_in"))
      (node (ref "IC2") (pin "118") (pinfunction "__GND_12_118") (pintype "power_in"))
      (node (ref "IC2") (pin "123") (pinfunction "__GND_13_123") (pintype "power_in"))
      (node (ref "IC2") (pin "131") (pinfunction "__GND_14_131") (pintype "power_in"))
      (node (ref "IC2") (pin "140") (pinfunction "__GND_15_140") (pintype "power_in"))
      (node (ref "IC2") (pin "145") (pinfunction "TP_145") (pintype "bidirectional"))
      (node (ref "IC2") (pin "19") (pinfunction "__GND_2_19") (pintype "power_in"))
      (node (ref "IC2") (pin "21") (pinfunction "__NCE_21") (pintype "bidirectional"))
      (node (ref "IC2") (pin "22") (pinfunction "__GND_3_22") (pintype "power_in"))
      (node (ref "IC2") (pin "27") (pinfunction "__GND_4_27") (pintype "power_in"))
      (node (ref "IC2") (pin "36") (pinfunction "__GNDA1_36") (pintype "power_in"))
      (node (ref "IC2") (pin "4") (pinfunction "__GND_1_4") (pintype "power_in"))
      (node (ref "IC2") (pin "41") (pinfunction "__GND_5_41") (pintype "power_in"))
      (node (ref "IC2") (pin "48") (pinfunction "__GND_6_48") (pintype "power_in"))
      (node (ref "IC2") (pin "57") (pinfunction "__GND_7_57") (pintype "power_in"))
      (node (ref "IC2") (pin "63") (pinfunction "__GND_8_63") (pintype "power_in"))
      (node (ref "IC2") (pin "79") (pinfunction "__GND_9_79") (pintype "power_in"))
      (node (ref "IC2") (pin "82") (pinfunction "__GND_10_82") (pintype "power_in"))
      (node (ref "IC2") (pin "94") (pinfunction "__MSEL0_94") (pintype "bidirectional"))
      (node (ref "IC2") (pin "95") (pinfunction "__GND_11_95") (pintype "power_in"))
      (node (ref "IC2") (pin "96") (pinfunction "__MSEL1_96") (pintype "bidirectional"))
      (node (ref "IC3") (pin "10") (pinfunction "GND_10") (pintype "power_in"))
      (node (ref "IC3") (pin "19") (pinfunction "G_19") (pintype "input"))
      (node (ref "IC4") (pin "10") (pinfunction "GND_10") (pintype "power_in"))
      (node (ref "IC5") (pin "3") (pinfunction "GND_3") (pintype "power_in"))
      (node (ref "IC6") (pin "1") (pinfunction "GND_1") (pintype "power_in"))
      (node (ref "IC7") (pin "3") (pinfunction "GND_3") (pintype "power_in"))
      (node (ref "IC8") (pin "2") (pinfunction "GND_2") (pintype "power_in"))
      (node (ref "IC9") (pin "4") (pinfunction "GND_4") (pintype "power_in"))
      (node (ref "J1") (pin "10") (pinfunction "10_10") (pintype "passive"))
      (node (ref "J1") (pin "2") (pinfunction "2_2") (pintype "passive"))
      (node (ref "J2") (pin "6") (pinfunction "VSS_6") (pintype "power_in"))
      (node (ref "J2") (pin "9") (pinfunction "VSS_9") (pintype "power_in"))
      (node (ref "Q1") (pin "2") (pinfunction "S_2") (pintype "passive"))
      (node (ref "Q2") (pin "1") (pinfunction "S_1") (pintype "passive"))
      (node (ref "Q2") (pin "4") (pinfunction "S_4") (pintype "passive"))
      (node (ref "Q3") (pin "2") (pinfunction "S_2") (pintype "passive"))
      (node (ref "R10") (pin "2") (pinfunction "2_2") (pintype "passive"))
      (node (ref "R18") (pin "1") (pinfunction "1_1") (pintype "passive"))
      (node (ref "R23") (pin "2") (pinfunction "2_2") (pintype "passive"))
      (node (ref "R26") (pin "1") (pinfunction "1_1") (pintype "passive"))
      (node (ref "R43") (pin "1") (pinfunction "1_1") (pintype "passive"))
      (node (ref "R45") (pin "2") (pinfunction "2_2") (pintype "passive"))
      (node (ref "R54") (pin "2") (pinfunction "2_2") (pintype "passive"))
      (node (ref "R57") (pin "1") (pinfunction "1_1") (pintype "passive"))
      (node (ref "R99") (pin "1") (pinfunction "1_1") (pintype "passive"))
      (node (ref "S1") (pin "A2") (pinfunction "1_A2") (pintype "passive"))
      (node (ref "S2") (pin "A2") (pinfunction "1_A2") (pintype "passive"))
      (node (ref "S3") (pin "A2") (pinfunction "1_A2") (pintype "passive"))
      (node (ref "TP4") (pin "TP") (pinfunction "TP_TP") (pintype "input"))
      (node (ref "TV26") (pin "1") (pinfunction "COM_1") (pintype "bidirectional"))
      (node (ref "U$1") (pin "2") (pinfunction "GND_2") (pintype "power_in"))
      (node (ref "U$3") (pin "2") (pinfunction "GND_2") (pintype "power_in"))
      (node (ref "U$5") (pin "A2") (pinfunction "GND_A2") (pintype "power_in"))
      (node (ref "U$5") (pin "B2") (pinfunction "GND_B2") (pintype "power_in"))
      (node (ref "U1") (pin "1") (pinfunction "GND_1") (pintype "bidirectional"))
      (node (ref "U1") (pin "15") (pinfunction "GND_15") (pintype "bidirectional"))
      (node (ref "U1") (pin "38") (pinfunction "GND_38") (pintype "bidirectional"))
      (node (ref "U1") (pin "GND") (pinfunction "GND_GND") (pintype "bidirectional"))
      (node (ref "USB2") (pin "GND") (pinfunction "GND_GND") (pintype "bidirectional"))
      (node (ref "USB3") (pin "P5") (pinfunction "GND_P5") (pintype "bidirectional"))
    )
    (net (code "167") (name "Net-(IC2-__CLK2)") (class "Default")
      (node (ref "IC2") (pin "24") (pinfunction "__CLK2_24") (pintype "input"))
      (node (ref "U$1") (pin "3") (pinfunction "FO_3") (pintype "output"))
    )
    (net (code "168") (name "Net-(IC2-__IO_6{slash}FLASH_NCS{slash}NCSO)") (class "Default")
      (node (ref "IC2") (pin "8") (pinfunction "__IO_6/FLASH_NCS/NCSO_8") (pintype "bidirectional"))
      (node (ref "TP2") (pin "TP") (pinfunction "TP_TP") (pintype "input"))
    )
    (net (code "169") (name "Net-(IC3A-A1)") (class "Default")
      (node (ref "IC3") (pin "2") (pinfunction "A1_2") (pintype "bidirectional"))
      (node (ref "RN1") (pin "8") (pinfunction "2_8") (pintype "passive"))
    )
    (net (code "170") (name "Net-(IC3A-A2)") (class "Default")
      (node (ref "IC3") (pin "3") (pinfunction "A2_3") (pintype "bidirectional"))
      (node (ref "RN1") (pin "7") (pinfunction "2_7") (pintype "passive"))
    )
    (net (code "171") (name "Net-(IC3A-A3)") (class "Default")
      (node (ref "IC3") (pin "4") (pinfunction "A3_4") (pintype "bidirectional"))
      (node (ref "RN1") (pin "6") (pinfunction "2_6") (pintype "passive"))
    )
    (net (code "172") (name "Net-(IC3A-A4)") (class "Default")
      (node (ref "IC3") (pin "5") (pinfunction "A4_5") (pintype "bidirectional"))
      (node (ref "RN1") (pin "5") (pinfunction "2_5") (pintype "passive"))
    )
    (net (code "173") (name "Net-(IC3A-A5)") (class "Default")
      (node (ref "IC3") (pin "6") (pinfunction "A5_6") (pintype "bidirectional"))
      (node (ref "RN2") (pin "8") (pinfunction "2_8") (pintype "passive"))
    )
    (net (code "174") (name "Net-(IC3A-A6)") (class "Default")
      (node (ref "IC3") (pin "7") (pinfunction "A6_7") (pintype "bidirectional"))
      (node (ref "RN2") (pin "7") (pinfunction "2_7") (pintype "passive"))
    )
    (net (code "175") (name "Net-(IC3A-A7)") (class "Default")
      (node (ref "IC3") (pin "8") (pinfunction "A7_8") (pintype "bidirectional"))
      (node (ref "RN2") (pin "6") (pinfunction "2_6") (pintype "passive"))
    )
    (net (code "176") (name "Net-(IC3A-A8)") (class "Default")
      (node (ref "IC3") (pin "9") (pinfunction "A8_9") (pintype "bidirectional"))
      (node (ref "RN2") (pin "5") (pinfunction "2_5") (pintype "passive"))
    )
    (net (code "177") (name "Net-(IC4A-A1)") (class "Default")
      (node (ref "IC4") (pin "2") (pinfunction "A1_2") (pintype "bidirectional"))
      (node (ref "RN7") (pin "8") (pinfunction "2_8") (pintype "passive"))
    )
    (net (code "178") (name "Net-(IC4A-A2)") (class "Default")
      (node (ref "IC4") (pin "3") (pinfunction "A2_3") (pintype "bidirectional"))
      (node (ref "RN7") (pin "7") (pinfunction "2_7") (pintype "passive"))
    )
    (net (code "179") (name "Net-(IC4A-A3)") (class "Default")
      (node (ref "IC4") (pin "4") (pinfunction "A3_4") (pintype "bidirectional"))
      (node (ref "RN7") (pin "6") (pinfunction "2_6") (pintype "passive"))
    )
    (net (code "180") (name "Net-(IC4A-A4)") (class "Default")
      (node (ref "IC4") (pin "5") (pinfunction "A4_5") (pintype "bidirectional"))
      (node (ref "RN7") (pin "5") (pinfunction "2_5") (pintype "passive"))
    )
    (net (code "181") (name "Net-(IC4A-A5)") (class "Default")
      (node (ref "IC4") (pin "6") (pinfunction "A5_6") (pintype "bidirectional"))
      (node (ref "RN8") (pin "8") (pinfunction "2_8") (pintype "passive"))
    )
    (net (code "182") (name "Net-(IC4A-A6)") (class "Default")
      (node (ref "IC4") (pin "7") (pinfunction "A6_7") (pintype "bidirectional"))
      (node (ref "RN8") (pin "7") (pinfunction "2_7") (pintype "passive"))
    )
    (net (code "183") (name "Net-(IC4A-A7)") (class "Default")
      (node (ref "IC4") (pin "8") (pinfunction "A7_8") (pintype "bidirectional"))
      (node (ref "RN8") (pin "6") (pinfunction "2_6") (pintype "passive"))
    )
    (net (code "184") (name "Net-(IC4A-A8)") (class "Default")
      (node (ref "IC4") (pin "9") (pinfunction "A8_9") (pintype "bidirectional"))
      (node (ref "RN8") (pin "5") (pinfunction "2_5") (pintype "passive"))
    )
    (net (code "185") (name "Net-(IC6-BST)") (class "Default")
      (node (ref "C43") (pin "2") (pinfunction "2_2") (pintype "passive"))
      (node (ref "IC6") (pin "6") (pinfunction "BST_6") (pintype "passive"))
    )
    (net (code "186") (name "Net-(IC6-EN)") (class "Default")
      (node (ref "IC6") (pin "5") (pinfunction "EN_5") (pintype "input"))
      (node (ref "R12") (pin "1") (pinfunction "1_1") (pintype "passive"))
    )
    (net (code "187") (name "Net-(IC7-DM)") (class "Default")
      (node (ref "IC7") (pin "2") (pinfunction "DM_2") (pintype "passive"))
      (node (ref "USB3") (pin "P2") (pinfunction "D-_P2") (pintype "bidirectional"))
    )
    (net (code "188") (name "Net-(IC7-DP)") (class "Default")
      (node (ref "IC7") (pin "1") (pinfunction "DP_1") (pintype "passive"))
      (node (ref "USB3") (pin "P3") (pinfunction "D+_P3") (pintype "bidirectional"))
    )
    (net (code "189") (name "Net-(IC10A-A1)") (class "Default")
      (node (ref "IC10") (pin "2") (pinfunction "A1_2") (pintype "bidirectional"))
      (node (ref "RN3") (pin "8") (pinfunction "2_8") (pintype "passive"))
    )
    (net (code "190") (name "Net-(IC10A-A2)") (class "Default")
      (node (ref "IC10") (pin "3") (pinfunction "A2_3") (pintype "bidirectional"))
      (node (ref "RN3") (pin "7") (pinfunction "2_7") (pintype "passive"))
    )
    (net (code "191") (name "Net-(IC10A-A3)") (class "Default")
      (node (ref "IC10") (pin "4") (pinfunction "A3_4") (pintype "bidirectional"))
      (node (ref "RN3") (pin "6") (pinfunction "2_6") (pintype "passive"))
    )
    (net (code "192") (name "Net-(IC10A-A4)") (class "Default")
      (node (ref "IC10") (pin "5") (pinfunction "A4_5") (pintype "bidirectional"))
      (node (ref "RN3") (pin "5") (pinfunction "2_5") (pintype "passive"))
    )
    (net (code "193") (name "Net-(IC10A-A5)") (class "Default")
      (node (ref "IC10") (pin "6") (pinfunction "A5_6") (pintype "bidirectional"))
      (node (ref "RN4") (pin "8") (pinfunction "2_8") (pintype "passive"))
    )
    (net (code "194") (name "Net-(IC10A-A6)") (class "Default")
      (node (ref "IC10") (pin "7") (pinfunction "A6_7") (pintype "bidirectional"))
      (node (ref "RN4") (pin "7") (pinfunction "2_7") (pintype "passive"))
    )
    (net (code "195") (name "Net-(IC10A-A7)") (class "Default")
      (node (ref "IC10") (pin "8") (pinfunction "A7_8") (pintype "bidirectional"))
      (node (ref "RN4") (pin "6") (pinfunction "2_6") (pintype "passive"))
    )
    (net (code "196") (name "Net-(IC10A-A8)") (class "Default")
      (node (ref "IC10") (pin "9") (pinfunction "A8_9") (pintype "bidirectional"))
      (node (ref "RN4") (pin "5") (pinfunction "2_5") (pintype "passive"))
    )
    (net (code "197") (name "Net-(IC11A-A1)") (class "Default")
      (node (ref "IC11") (pin "2") (pinfunction "A1_2") (pintype "bidirectional"))
      (node (ref "RN5") (pin "8") (pinfunction "2_8") (pintype "passive"))
    )
    (net (code "198") (name "Net-(IC11A-A2)") (class "Default")
      (node (ref "IC11") (pin "3") (pinfunction "A2_3") (pintype "bidirectional"))
      (node (ref "RN5") (pin "7") (pinfunction "2_7") (pintype "passive"))
    )
    (net (code "199") (name "Net-(IC11A-A3)") (class "Default")
      (node (ref "IC11") (pin "4") (pinfunction "A3_4") (pintype "bidirectional"))
      (node (ref "RN5") (pin "6") (pinfunction "2_6") (pintype "passive"))
    )
    (net (code "200") (name "Net-(IC11A-A4)") (class "Default")
      (node (ref "IC11") (pin "5") (pinfunction "A4_5") (pintype "bidirectional"))
      (node (ref "RN5") (pin "5") (pinfunction "2_5") (pintype "passive"))
    )
    (net (code "201") (name "Net-(IC11A-A5)") (class "Default")
      (node (ref "IC11") (pin "6") (pinfunction "A5_6") (pintype "bidirectional"))
      (node (ref "RN6") (pin "8") (pinfunction "2_8") (pintype "passive"))
    )
    (net (code "202") (name "Net-(IC11A-A6)") (class "Default")
      (node (ref "IC11") (pin "7") (pinfunction "A6_7") (pintype "bidirectional"))
      (node (ref "RN6") (pin "7") (pinfunction "2_7") (pintype "passive"))
    )
    (net (code "203") (name "Net-(IC11A-A7)") (class "Default")
      (node (ref "IC11") (pin "8") (pinfunction "A7_8") (pintype "bidirectional"))
      (node (ref "RN6") (pin "6") (pinfunction "2_6") (pintype "passive"))
    )
    (net (code "204") (name "Net-(IC11A-A8)") (class "Default")
      (node (ref "IC11") (pin "9") (pinfunction "A8_9") (pintype "bidirectional"))
      (node (ref "RN6") (pin "5") (pinfunction "2_5") (pintype "passive"))
    )
    (net (code "205") (name "Net-(IC12-DM)") (class "Default")
      (node (ref "IC12") (pin "10") (pinfunction "DM_10") (pintype "bidirectional"))
      (node (ref "R36") (pin "1") (pinfunction "1_1") (pintype "passive"))
    )
    (net (code "206") (name "Net-(IC12-DP)") (class "Default")
      (node (ref "IC12") (pin "11") (pinfunction "DP_11") (pintype "bidirectional"))
      (node (ref "R35") (pin "1") (pinfunction "1_1") (pintype "passive"))
    )
    (net (code "207") (name "Net-(IC13C-O)") (class "Default")
      (node (ref "IC13") (pin "6") (pinfunction "O_6") (pintype "open_collector"))
      (node (ref "Q4") (pin "2") (pinfunction "G_2") (pintype "passive"))
      (node (ref "R25") (pin "2") (pinfunction "2_2") (pintype "passive"))
    )
    (net (code "208") (name "Net-(IC14-BST)") (class "Default")
      (node (ref "C42") (pin "2") (pinfunction "2_2") (pintype "passive"))
      (node (ref "IC14") (pin "6") (pinfunction "BST_6") (pintype "passive"))
    )
    (net (code "209") (name "Net-(IC14-EN)") (class "Default")
      (node (ref "IC14") (pin "5") (pinfunction "EN_5") (pintype "input"))
      (node (ref "R11") (pin "1") (pinfunction "1_1") (pintype "passive"))
    )
    (net (code "210") (name "Net-(IC14-FB)") (class "Default")
      (node (ref "IC14") (pin "4") (pinfunction "FB_4") (pintype "passive"))
      (node (ref "R1") (pin "1") (pinfunction "1_1") (pintype "passive"))
      (node (ref "R99") (pin "2") (pinfunction "2_2") (pintype "passive"))
    )
    (net (code "211") (name "Net-(LED1-PadC)") (class "Default")
      (node (ref "LED1") (pin "C") (pinfunction "C_C") (pintype "passive"))
      (node (ref "R21") (pin "1") (pinfunction "1_1") (pintype "passive"))
    )
    (net (code "212") (name "Net-(LED2-PadC)") (class "Default")
      (node (ref "LED2") (pin "C") (pinfunction "C_C") (pintype "passive"))
      (node (ref "R22") (pin "1") (pinfunction "1_1") (pintype "passive"))
    )
    (net (code "213") (name "Net-(LED3-PadC)") (class "Default")
      (node (ref "LED3") (pin "C") (pinfunction "C_C") (pintype "passive"))
      (node (ref "R23") (pin "1") (pinfunction "1_1") (pintype "passive"))
    )
    (net (code "214") (name "Net-(LED4-PadC)") (class "Default")
      (node (ref "LED4") (pin "C") (pinfunction "C_C") (pintype "passive"))
      (node (ref "R39") (pin "1") (pinfunction "1_1") (pintype "passive"))
    )
    (net (code "215") (name "Net-(LED5-PadC)") (class "Default")
      (node (ref "LED5") (pin "C") (pinfunction "C_C") (pintype "passive"))
      (node (ref "R40") (pin "1") (pinfunction "1_1") (pintype "passive"))
    )
    (net (code "216") (name "Net-(LED6-PadC)") (class "Default")
      (node (ref "LED6") (pin "C") (pinfunction "C_C") (pintype "passive"))
      (node (ref "R41") (pin "1") (pinfunction "1_1") (pintype "passive"))
    )
    (net (code "217") (name "Net-(Q2A-D)") (class "Default")
      (node (ref "Q2") (pin "3") (pinfunction "D_3") (pintype "passive"))
      (node (ref "R48") (pin "1") (pinfunction "1_1") (pintype "passive"))
    )
    (net (code "218") (name "Net-(Q2A-G)") (class "Default")
      (node (ref "Q2") (pin "5") (pinfunction "G_5") (pintype "passive"))
      (node (ref "Q2") (pin "6") (pinfunction "D_6") (pintype "passive"))
      (node (ref "R50") (pin "1") (pinfunction "1_1") (pintype "passive"))
    )
    (net (code "219") (name "Net-(Q2B-G)") (class "Default")
      (node (ref "Q2") (pin "2") (pinfunction "G_2") (pintype "passive"))
      (node (ref "R49") (pin "1") (pinfunction "1_1") (pintype "passive"))
    )
    (net (code "220") (name "Net-(Q3-D)") (class "Default")
      (node (ref "Q3") (pin "3") (pinfunction "D_3") (pintype "passive"))
      (node (ref "R52") (pin "1") (pinfunction "1_1") (pintype "passive"))
    )
    (net (code "221") (name "Net-(Q3-G)") (class "Default")
      (node (ref "Q3") (pin "1") (pinfunction "G_1") (pintype "passive"))
      (node (ref "R53") (pin "1") (pinfunction "1_1") (pintype "passive"))
      (node (ref "R54") (pin "1") (pinfunction "1_1") (pintype "passive"))
    )
    (net (code "222") (name "Net-(Q5A-D)") (class "Default")
      (node (ref "Q5") (pin "3") (pinfunction "D_3") (pintype "passive"))
      (node (ref "R14") (pin "2") (pinfunction "2_2") (pintype "passive"))
    )
    (net (code "223") (name "Net-(Q6A-D)") (class "Default")
      (node (ref "Q6") (pin "3") (pinfunction "D_3") (pintype "passive"))
      (node (ref "R29") (pin "1") (pinfunction "1_1") (pintype "passive"))
    )
    (net (code "224") (name "Net-(Q6B-D)") (class "Default")
      (node (ref "Q6") (pin "6") (pinfunction "D_6") (pintype "passive"))
      (node (ref "R33") (pin "1") (pinfunction "1_1") (pintype "passive"))
    )
    (net (code "225") (name "Net-(R26-Pad2)") (class "Default")
      (node (ref "R26") (pin "2") (pinfunction "2_2") (pintype "passive"))
      (node (ref "R44") (pin "1") (pinfunction "1_1") (pintype "passive"))
      (node (ref "R46") (pin "2") (pinfunction "2_2") (pintype "passive"))
    )
    (net (code "226") (name "Net-(T2A-G)") (class "Default")
      (node (ref "R47") (pin "1") (pinfunction "1_1") (pintype "passive"))
      (node (ref "R48") (pin "2") (pinfunction "2_2") (pintype "passive"))
      (node (ref "T2") (pin "1") (pinfunction "G_1") (pintype "passive"))
    )
    (net (code "227") (name "Net-(T2B-G)") (class "Default")
      (node (ref "C54") (pin "1") (pinfunction "1_1") (pintype "passive"))
      (node (ref "R51") (pin "1") (pinfunction "1_1") (pintype "passive"))
      (node (ref "R52") (pin "2") (pinfunction "2_2") (pintype "passive"))
      (node (ref "T2") (pin "3") (pinfunction "G_3") (pintype "passive"))
    )
    (net (code "228") (name "PE") (class "Default")
      (node (ref "C50") (pin "1") (pinfunction "1_1") (pintype "passive"))
      (node (ref "J2") (pin "P1") (pinfunction "SHIELD_P1") (pintype "passive"))
      (node (ref "J2") (pin "P2") (pinfunction "SHIELD_P2") (pintype "passive"))
      (node (ref "J2") (pin "P3") (pinfunction "SHIELD_P3") (pintype "passive"))
      (node (ref "J2") (pin "P4") (pinfunction "SHIELD_P4") (pintype "passive"))
      (node (ref "R45") (pin "1") (pinfunction "1_1") (pintype "passive"))
      (node (ref "USB2") (pin "P$5") (pinfunction "SHIELD_P$5") (pintype "passive"))
      (node (ref "USB2") (pin "P$6") (pinfunction "SHIELD_P$6") (pintype "passive"))
      (node (ref "USB3") (pin "S1") (pinfunction "SHIELD_S1") (pintype "passive"))
      (node (ref "USB3") (pin "S2") (pinfunction "SHIELD_S2") (pintype "passive"))
      (node (ref "USB3") (pin "S3") (pinfunction "SHIELD_S3") (pintype "passive"))
      (node (ref "USB3") (pin "S4") (pinfunction "SHIELD_S4") (pintype "passive"))
      (node (ref "USB3") (pin "S5") (pinfunction "SHIELD_S5") (pintype "passive"))
      (node (ref "USB3") (pin "S6") (pinfunction "SHIELD_S6") (pintype "passive"))
    )
    (net (code "229") (name "unconnected-(CONN1-BUSACK-PadA26)") (class "Default")
      (node (ref "CONN1") (pin "A26") (pinfunction "BUSACK_A26") (pintype "bidirectional"))
    )
    (net (code "230") (name "unconnected-(CONN1-BUSREQ-PadA19)") (class "Default")
      (node (ref "CONN1") (pin "A19") (pinfunction "BUSREQ_A19") (pintype "bidirectional"))
    )
    (net (code "231") (name "unconnected-(CONN1-HALT-PadB15)") (class "Default")
      (node (ref "CONN1") (pin "B15") (pinfunction "HALT_B15") (pintype "bidirectional"))
    )
    (net (code "232") (name "unconnected-(CONN1-NC-PadB28)") (class "Default")
      (node (ref "CONN1") (pin "B28") (pinfunction "NC_B28") (pintype "bidirectional"))
    )
    (net (code "233") (name "unconnected-(CONN1-U-PadA18)") (class "Default")
      (node (ref "CONN1") (pin "A18") (pinfunction "U_A18") (pintype "bidirectional"))
    )
    (net (code "234") (name "unconnected-(CONN1-V-PadA17)") (class "Default")
      (node (ref "CONN1") (pin "A17") (pinfunction "V_A17") (pintype "bidirectional"))
    )
    (net (code "235") (name "unconnected-(CONN1-YL-PadA16)") (class "Default")
      (node (ref "CONN1") (pin "A16") (pinfunction "YL_A16") (pintype "bidirectional"))
    )
    (net (code "236") (name "unconnected-(IC2-__CLK5-Pad90)") (class "Default")
      (node (ref "IC2") (pin "90") (pinfunction "__CLK5_90") (pintype "input"))
    )
    (net (code "237") (name "unconnected-(IC2-__CLK6-Pad89)") (class "Default")
      (node (ref "IC2") (pin "89") (pinfunction "__CLK6_89") (pintype "input"))
    )
    (net (code "238") (name "unconnected-(IC2-__CLK7-Pad88)") (class "Default")
      (node (ref "IC2") (pin "88") (pinfunction "__CLK7_88") (pintype "input"))
    )
    (net (code "239") (name "unconnected-(J1-Pad6)") (class "Default")
      (node (ref "J1") (pin "6") (pinfunction "6_6") (pintype "passive"))
    )
    (net (code "240") (name "unconnected-(J1-Pad7)") (class "Default")
      (node (ref "J1") (pin "7") (pinfunction "7_7") (pintype "passive"))
    )
    (net (code "241") (name "unconnected-(J1-Pad8)") (class "Default")
      (node (ref "J1") (pin "8") (pinfunction "8_8") (pintype "passive"))
    )
    (net (code "242") (name "unconnected-(J2-DETECT_SWITCH-Pad10)") (class "Default")
      (node (ref "J2") (pin "10") (pinfunction "DETECT_SWITCH_10") (pintype "passive"))
    )
    (net (code "243") (name "unconnected-(U1-CLK-Pad20)") (class "Default")
      (node (ref "U1") (pin "20") (pinfunction "CLK_20") (pintype "bidirectional"))
    )
    (net (code "244") (name "unconnected-(U1-CMD-Pad19)") (class "Default")
      (node (ref "U1") (pin "19") (pinfunction "CMD_19") (pintype "bidirectional"))
    )
    (net (code "245") (name "unconnected-(U1-NC-Pad32)") (class "Default")
      (node (ref "U1") (pin "32") (pinfunction "NC_32") (pintype "bidirectional"))
    )
    (net (code "246") (name "unconnected-(U1-SD1-Pad22)") (class "Default")
      (node (ref "U1") (pin "22") (pinfunction "SD1_22") (pintype "bidirectional"))
    )
    (net (code "247") (name "unconnected-(U1-SD2-Pad17)") (class "Default")
      (node (ref "U1") (pin "17") (pinfunction "SD2_17") (pintype "bidirectional"))
    )
    (net (code "248") (name "unconnected-(U1-SD3-Pad18)") (class "Default")
      (node (ref "U1") (pin "18") (pinfunction "SD3_18") (pintype "bidirectional"))
    )
    (net (code "249") (name "unconnected-(U1-SDO-Pad21)") (class "Default")
      (node (ref "U1") (pin "21") (pinfunction "SDO_21") (pintype "bidirectional"))
    )
    (net (code "250") (name "unconnected-(U1-SENSOR_VN-Pad5)") (class "Default")
      (node (ref "U1") (pin "5") (pinfunction "SENSOR_VN_5") (pintype "input"))
    )
    (net (code "251") (name "unconnected-(USB3-USBID-PadP4)") (class "Default")
      (node (ref "USB3") (pin "P4") (pinfunction "USBID_P4") (pintype "bidirectional"))
    )
    (net (code "252") (name "unconnected-(USB3-VUSB-PadP1)") (class "Default")
      (node (ref "USB3") (pin "P1") (pinfunction "VUSB_P1") (pintype "bidirectional"))
    )
  )
)
